# DAC7828_main_V10101010.net
KiCad netlist of a schematic drawn in Altium Designer
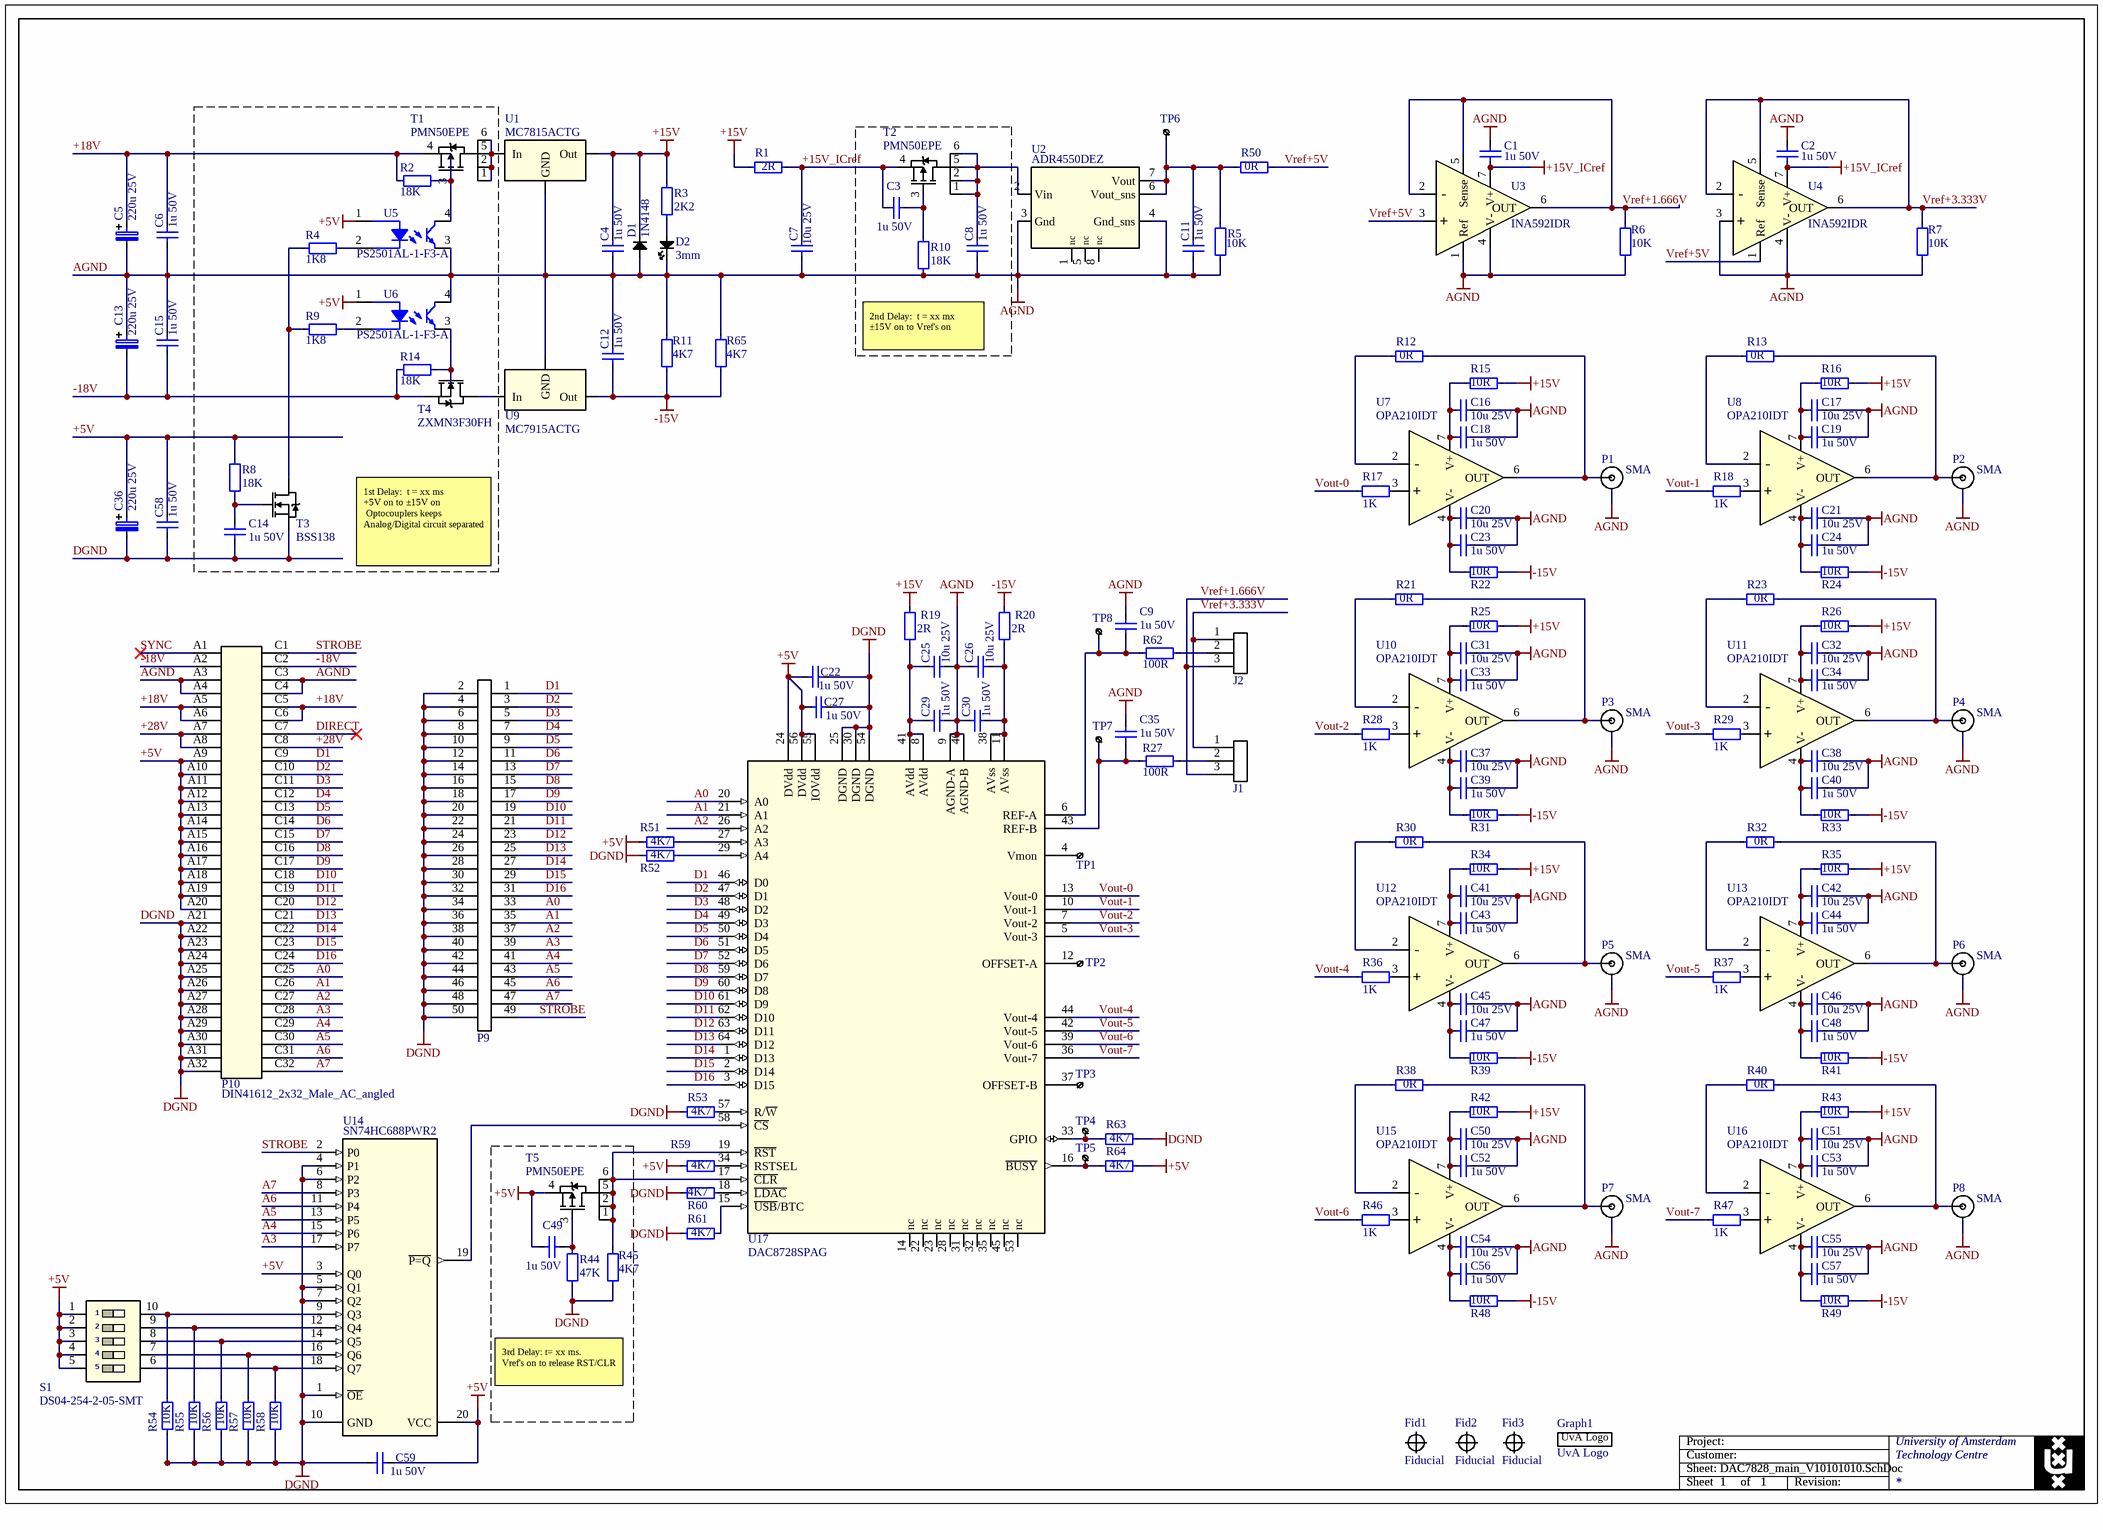
[diagram p0: DAC7828_main_V10101010.SchDoc]

(export (version "E")
  (design (tool "Eeschema 10.0.6"))
  (components
    (comp (ref "C1")
      (value "1u 50V")
      (footprint "cap0603MD")
      (fields
        (field (name "VOLTAGE") "50V")
        (field (name "AUTHOR") "Twe")
        (field (name "CHECKED BY") "Unchecked")
      )
      (libsource (lib "TC_Parts") (part "capacitor"))
    )
    (comp (ref "C2")
      (value "1u 50V")
      (footprint "cap0603MD")
      (fields
        (field (name "VOLTAGE") "50V")
        (field (name "AUTHOR") "Twe")
        (field (name "CHECKED BY") "Unchecked")
      )
      (libsource (lib "TC_Parts") (part "capacitor"))
    )
    (comp (ref "C3")
      (value "1u 50V")
      (footprint "cap0603MD")
      (fields
        (field (name "VOLTAGE") "50V")
        (field (name "AUTHOR") "Twe")
        (field (name "CHECKED BY") "Unchecked")
      )
      (libsource (lib "TC_Parts") (part "capacitor"))
    )
    (comp (ref "C4")
      (value "1u 50V")
      (footprint "cap0603MD")
      (fields
        (field (name "VOLTAGE") "50V")
        (field (name "AUTHOR") "Twe")
        (field (name "CHECKED BY") "Unchecked")
      )
      (libsource (lib "TC_Parts") (part "capacitor"))
    )
    (comp (ref "C5")
      (value "220u 25V")
      (footprint "capAluSmd_d8H10mm")
      (description "Cap Alu SMD d8h11, ±20%")
      (fields
        (field (name "MANUFACTURER") "Kemet")
        (field (name "VOLTAGE") "25V")
        (field (name "AUTHOR") "EB")
        (field (name "CHECKED BY") "Unchecked")
      )
      (libsource (lib "TC_Parts") (part "capuni"))
    )
    (comp (ref "C6")
      (value "1u 50V")
      (footprint "cap0603MD")
      (fields
        (field (name "VOLTAGE") "50V")
        (field (name "AUTHOR") "Twe")
        (field (name "CHECKED BY") "Unchecked")
      )
      (libsource (lib "TC_Parts") (part "capacitor"))
    )
    (comp (ref "C7")
      (value "10u 25V")
      (footprint "cap0805MD")
      (fields
        (field (name "VOLTAGE") "25V")
        (field (name "AUTHOR") "EB")
        (field (name "CHECKED BY") "Unchecked")
      )
      (libsource (lib "TC_Parts") (part "capacitor"))
    )
    (comp (ref "C8")
      (value "1u 50V")
      (footprint "cap0603MD")
      (fields
        (field (name "VOLTAGE") "50V")
        (field (name "AUTHOR") "Twe")
        (field (name "CHECKED BY") "Unchecked")
      )
      (libsource (lib "TC_Parts") (part "capacitor"))
    )
    (comp (ref "C9")
      (value "1u 50V")
      (footprint "cap0603MD")
      (fields
        (field (name "VOLTAGE") "50V")
        (field (name "AUTHOR") "Twe")
        (field (name "CHECKED BY") "Unchecked")
      )
      (libsource (lib "TC_Parts") (part "capacitor"))
    )
    (comp (ref "C11")
      (value "1u 50V")
      (footprint "cap0603MD")
      (fields
        (field (name "VOLTAGE") "50V")
        (field (name "AUTHOR") "Twe")
        (field (name "CHECKED BY") "Unchecked")
      )
      (libsource (lib "TC_Parts") (part "capacitor"))
    )
    (comp (ref "C12")
      (value "1u 50V")
      (footprint "cap0603MD")
      (fields
        (field (name "VOLTAGE") "50V")
        (field (name "AUTHOR") "Twe")
        (field (name "CHECKED BY") "Unchecked")
      )
      (libsource (lib "TC_Parts") (part "capacitor"))
    )
    (comp (ref "C13")
      (value "220u 25V")
      (footprint "capAluSmd_d8H10mm")
      (description "Cap Alu SMD d8h11, ±20%")
      (fields
        (field (name "MANUFACTURER") "Kemet")
        (field (name "VOLTAGE") "25V")
        (field (name "AUTHOR") "EB")
        (field (name "CHECKED BY") "Unchecked")
      )
      (libsource (lib "TC_Parts") (part "capuni"))
    )
    (comp (ref "C14")
      (value "1u 50V")
      (footprint "cap0603MD")
      (fields
        (field (name "VOLTAGE") "50V")
        (field (name "AUTHOR") "Twe")
        (field (name "CHECKED BY") "Unchecked")
      )
      (libsource (lib "TC_Parts") (part "capacitor"))
    )
    (comp (ref "C15")
      (value "1u 50V")
      (footprint "cap0603MD")
      (fields
        (field (name "VOLTAGE") "50V")
        (field (name "AUTHOR") "Twe")
        (field (name "CHECKED BY") "Unchecked")
      )
      (libsource (lib "TC_Parts") (part "capacitor"))
    )
    (comp (ref "C16")
      (value "10u 25V")
      (footprint "cap0805MD")
      (fields
        (field (name "VOLTAGE") "25V")
        (field (name "AUTHOR") "EB")
        (field (name "CHECKED BY") "Unchecked")
      )
      (libsource (lib "TC_Parts") (part "capacitor"))
    )
    (comp (ref "C17")
      (value "10u 25V")
      (footprint "cap0805MD")
      (fields
        (field (name "VOLTAGE") "25V")
        (field (name "AUTHOR") "EB")
        (field (name "CHECKED BY") "Unchecked")
      )
      (libsource (lib "TC_Parts") (part "capacitor"))
    )
    (comp (ref "C18")
      (value "1u 50V")
      (footprint "cap0603MD")
      (fields
        (field (name "VOLTAGE") "50V")
        (field (name "AUTHOR") "Twe")
        (field (name "CHECKED BY") "Unchecked")
      )
      (libsource (lib "TC_Parts") (part "capacitor"))
    )
    (comp (ref "C19")
      (value "1u 50V")
      (footprint "cap0603MD")
      (fields
        (field (name "VOLTAGE") "50V")
        (field (name "AUTHOR") "Twe")
        (field (name "CHECKED BY") "Unchecked")
      )
      (libsource (lib "TC_Parts") (part "capacitor"))
    )
    (comp (ref "C20")
      (value "10u 25V")
      (footprint "cap0805MD")
      (fields
        (field (name "VOLTAGE") "25V")
        (field (name "AUTHOR") "EB")
        (field (name "CHECKED BY") "Unchecked")
      )
      (libsource (lib "TC_Parts") (part "capacitor"))
    )
    (comp (ref "C21")
      (value "10u 25V")
      (footprint "cap0805MD")
      (fields
        (field (name "VOLTAGE") "25V")
        (field (name "AUTHOR") "EB")
        (field (name "CHECKED BY") "Unchecked")
      )
      (libsource (lib "TC_Parts") (part "capacitor"))
    )
    (comp (ref "C22")
      (value "1u 50V")
      (footprint "cap0603MD")
      (fields
        (field (name "VOLTAGE") "50V")
        (field (name "AUTHOR") "Twe")
        (field (name "CHECKED BY") "Unchecked")
      )
      (libsource (lib "TC_Parts") (part "capacitor"))
    )
    (comp (ref "C23")
      (value "1u 50V")
      (footprint "cap0603MD")
      (fields
        (field (name "VOLTAGE") "50V")
        (field (name "AUTHOR") "Twe")
        (field (name "CHECKED BY") "Unchecked")
      )
      (libsource (lib "TC_Parts") (part "capacitor"))
    )
    (comp (ref "C24")
      (value "1u 50V")
      (footprint "cap0603MD")
      (fields
        (field (name "VOLTAGE") "50V")
        (field (name "AUTHOR") "Twe")
        (field (name "CHECKED BY") "Unchecked")
      )
      (libsource (lib "TC_Parts") (part "capacitor"))
    )
    (comp (ref "C25")
      (value "10u 25V")
      (footprint "cap0805MD")
      (fields
        (field (name "VOLTAGE") "25V")
        (field (name "AUTHOR") "EB")
        (field (name "CHECKED BY") "Unchecked")
      )
      (libsource (lib "TC_Parts") (part "capacitor"))
    )
    (comp (ref "C26")
      (value "10u 25V")
      (footprint "cap0805MD")
      (fields
        (field (name "VOLTAGE") "25V")
        (field (name "AUTHOR") "EB")
        (field (name "CHECKED BY") "Unchecked")
      )
      (libsource (lib "TC_Parts") (part "capacitor"))
    )
    (comp (ref "C27")
      (value "1u 50V")
      (footprint "cap0603MD")
      (fields
        (field (name "VOLTAGE") "50V")
        (field (name "AUTHOR") "Twe")
        (field (name "CHECKED BY") "Unchecked")
      )
      (libsource (lib "TC_Parts") (part "capacitor"))
    )
    (comp (ref "C29")
      (value "1u 50V")
      (footprint "cap0603MD")
      (fields
        (field (name "VOLTAGE") "50V")
        (field (name "AUTHOR") "Twe")
        (field (name "CHECKED BY") "Unchecked")
      )
      (libsource (lib "TC_Parts") (part "capacitor"))
    )
    (comp (ref "C30")
      (value "1u 50V")
      (footprint "cap0603MD")
      (fields
        (field (name "VOLTAGE") "50V")
        (field (name "AUTHOR") "Twe")
        (field (name "CHECKED BY") "Unchecked")
      )
      (libsource (lib "TC_Parts") (part "capacitor"))
    )
    (comp (ref "C31")
      (value "10u 25V")
      (footprint "cap0805MD")
      (fields
        (field (name "VOLTAGE") "25V")
        (field (name "AUTHOR") "EB")
        (field (name "CHECKED BY") "Unchecked")
      )
      (libsource (lib "TC_Parts") (part "capacitor"))
    )
    (comp (ref "C32")
      (value "10u 25V")
      (footprint "cap0805MD")
      (fields
        (field (name "VOLTAGE") "25V")
        (field (name "AUTHOR") "EB")
        (field (name "CHECKED BY") "Unchecked")
      )
      (libsource (lib "TC_Parts") (part "capacitor"))
    )
    (comp (ref "C33")
      (value "1u 50V")
      (footprint "cap0603MD")
      (fields
        (field (name "VOLTAGE") "50V")
        (field (name "AUTHOR") "Twe")
        (field (name "CHECKED BY") "Unchecked")
      )
      (libsource (lib "TC_Parts") (part "capacitor"))
    )
    (comp (ref "C34")
      (value "1u 50V")
      (footprint "cap0603MD")
      (fields
        (field (name "VOLTAGE") "50V")
        (field (name "AUTHOR") "Twe")
        (field (name "CHECKED BY") "Unchecked")
      )
      (libsource (lib "TC_Parts") (part "capacitor"))
    )
    (comp (ref "C35")
      (value "1u 50V")
      (footprint "cap0603MD")
      (fields
        (field (name "VOLTAGE") "50V")
        (field (name "AUTHOR") "Twe")
        (field (name "CHECKED BY") "Unchecked")
      )
      (libsource (lib "TC_Parts") (part "capacitor"))
    )
    (comp (ref "C36")
      (value "220u 25V")
      (footprint "capAluSmd_d8H10mm")
      (description "Cap Alu SMD d8h11, ±20%")
      (fields
        (field (name "MANUFACTURER") "Kemet")
        (field (name "VOLTAGE") "25V")
        (field (name "AUTHOR") "EB")
        (field (name "CHECKED BY") "Unchecked")
      )
      (libsource (lib "TC_Parts") (part "capuni"))
    )
    (comp (ref "C37")
      (value "10u 25V")
      (footprint "cap0805MD")
      (fields
        (field (name "VOLTAGE") "25V")
        (field (name "AUTHOR") "EB")
        (field (name "CHECKED BY") "Unchecked")
      )
      (libsource (lib "TC_Parts") (part "capacitor"))
    )
    (comp (ref "C38")
      (value "10u 25V")
      (footprint "cap0805MD")
      (fields
        (field (name "VOLTAGE") "25V")
        (field (name "AUTHOR") "EB")
        (field (name "CHECKED BY") "Unchecked")
      )
      (libsource (lib "TC_Parts") (part "capacitor"))
    )
    (comp (ref "C39")
      (value "1u 50V")
      (footprint "cap0603MD")
      (fields
        (field (name "VOLTAGE") "50V")
        (field (name "AUTHOR") "Twe")
        (field (name "CHECKED BY") "Unchecked")
      )
      (libsource (lib "TC_Parts") (part "capacitor"))
    )
    (comp (ref "C40")
      (value "1u 50V")
      (footprint "cap0603MD")
      (fields
        (field (name "VOLTAGE") "50V")
        (field (name "AUTHOR") "Twe")
        (field (name "CHECKED BY") "Unchecked")
      )
      (libsource (lib "TC_Parts") (part "capacitor"))
    )
    (comp (ref "C41")
      (value "10u 25V")
      (footprint "cap0805MD")
      (fields
        (field (name "VOLTAGE") "25V")
        (field (name "AUTHOR") "EB")
        (field (name "CHECKED BY") "Unchecked")
      )
      (libsource (lib "TC_Parts") (part "capacitor"))
    )
    (comp (ref "C42")
      (value "10u 25V")
      (footprint "cap0805MD")
      (fields
        (field (name "VOLTAGE") "25V")
        (field (name "AUTHOR") "EB")
        (field (name "CHECKED BY") "Unchecked")
      )
      (libsource (lib "TC_Parts") (part "capacitor"))
    )
    (comp (ref "C43")
      (value "1u 50V")
      (footprint "cap0603MD")
      (fields
        (field (name "VOLTAGE") "50V")
        (field (name "AUTHOR") "Twe")
        (field (name "CHECKED BY") "Unchecked")
      )
      (libsource (lib "TC_Parts") (part "capacitor"))
    )
    (comp (ref "C44")
      (value "1u 50V")
      (footprint "cap0603MD")
      (fields
        (field (name "VOLTAGE") "50V")
        (field (name "AUTHOR") "Twe")
        (field (name "CHECKED BY") "Unchecked")
      )
      (libsource (lib "TC_Parts") (part "capacitor"))
    )
    (comp (ref "C45")
      (value "10u 25V")
      (footprint "cap0805MD")
      (fields
        (field (name "VOLTAGE") "25V")
        (field (name "AUTHOR") "EB")
        (field (name "CHECKED BY") "Unchecked")
      )
      (libsource (lib "TC_Parts") (part "capacitor"))
    )
    (comp (ref "C46")
      (value "10u 25V")
      (footprint "cap0805MD")
      (fields
        (field (name "VOLTAGE") "25V")
        (field (name "AUTHOR") "EB")
        (field (name "CHECKED BY") "Unchecked")
      )
      (libsource (lib "TC_Parts") (part "capacitor"))
    )
    (comp (ref "C47")
      (value "1u 50V")
      (footprint "cap0603MD")
      (fields
        (field (name "VOLTAGE") "50V")
        (field (name "AUTHOR") "Twe")
        (field (name "CHECKED BY") "Unchecked")
      )
      (libsource (lib "TC_Parts") (part "capacitor"))
    )
    (comp (ref "C48")
      (value "1u 50V")
      (footprint "cap0603MD")
      (fields
        (field (name "VOLTAGE") "50V")
        (field (name "AUTHOR") "Twe")
        (field (name "CHECKED BY") "Unchecked")
      )
      (libsource (lib "TC_Parts") (part "capacitor"))
    )
    (comp (ref "C49")
      (value "1u 50V")
      (footprint "cap0603MD")
      (fields
        (field (name "VOLTAGE") "50V")
        (field (name "AUTHOR") "Twe")
        (field (name "CHECKED BY") "Unchecked")
      )
      (libsource (lib "TC_Parts") (part "capacitor"))
    )
    (comp (ref "C50")
      (value "10u 25V")
      (footprint "cap0805MD")
      (fields
        (field (name "VOLTAGE") "25V")
        (field (name "AUTHOR") "EB")
        (field (name "CHECKED BY") "Unchecked")
      )
      (libsource (lib "TC_Parts") (part "capacitor"))
    )
    (comp (ref "C51")
      (value "10u 25V")
      (footprint "cap0805MD")
      (fields
        (field (name "VOLTAGE") "25V")
        (field (name "AUTHOR") "EB")
        (field (name "CHECKED BY") "Unchecked")
      )
      (libsource (lib "TC_Parts") (part "capacitor"))
    )
    (comp (ref "C52")
      (value "1u 50V")
      (footprint "cap0603MD")
      (fields
        (field (name "VOLTAGE") "50V")
        (field (name "AUTHOR") "Twe")
        (field (name "CHECKED BY") "Unchecked")
      )
      (libsource (lib "TC_Parts") (part "capacitor"))
    )
    (comp (ref "C53")
      (value "1u 50V")
      (footprint "cap0603MD")
      (fields
        (field (name "VOLTAGE") "50V")
        (field (name "AUTHOR") "Twe")
        (field (name "CHECKED BY") "Unchecked")
      )
      (libsource (lib "TC_Parts") (part "capacitor"))
    )
    (comp (ref "C54")
      (value "10u 25V")
      (footprint "cap0805MD")
      (fields
        (field (name "VOLTAGE") "25V")
        (field (name "AUTHOR") "EB")
        (field (name "CHECKED BY") "Unchecked")
      )
      (libsource (lib "TC_Parts") (part "capacitor"))
    )
    (comp (ref "C55")
      (value "10u 25V")
      (footprint "cap0805MD")
      (fields
        (field (name "VOLTAGE") "25V")
        (field (name "AUTHOR") "EB")
        (field (name "CHECKED BY") "Unchecked")
      )
      (libsource (lib "TC_Parts") (part "capacitor"))
    )
    (comp (ref "C56")
      (value "1u 50V")
      (footprint "cap0603MD")
      (fields
        (field (name "VOLTAGE") "50V")
        (field (name "AUTHOR") "Twe")
        (field (name "CHECKED BY") "Unchecked")
      )
      (libsource (lib "TC_Parts") (part "capacitor"))
    )
    (comp (ref "C57")
      (value "1u 50V")
      (footprint "cap0603MD")
      (fields
        (field (name "VOLTAGE") "50V")
        (field (name "AUTHOR") "Twe")
        (field (name "CHECKED BY") "Unchecked")
      )
      (libsource (lib "TC_Parts") (part "capacitor"))
    )
    (comp (ref "C58")
      (value "1u 50V")
      (footprint "cap0603MD")
      (fields
        (field (name "VOLTAGE") "50V")
        (field (name "AUTHOR") "Twe")
        (field (name "CHECKED BY") "Unchecked")
      )
      (libsource (lib "TC_Parts") (part "capacitor"))
    )
    (comp (ref "C59")
      (value "1u 50V")
      (footprint "cap0603MD")
      (fields
        (field (name "VOLTAGE") "50V")
        (field (name "AUTHOR") "Twe")
        (field (name "CHECKED BY") "Unchecked")
      )
      (libsource (lib "TC_Parts") (part "capacitor"))
    )
    (comp (ref "D1")
      (value "1N4148")
      (footprint "SOD2513X100N")
      (description "Small Signal Diode, Single, 100 V, 150 mA, 1 V, 4 ns, 350 mA")
      (fields
        (field (name "MANUFACTURER") "Multicomp")
        (field (name "AUTHOR") "Twe")
        (field (name "CHECKED BY") "PCB")
      )
      (libsource (lib "TC_Parts") (part "diode_CA"))
    )
    (comp (ref "D2")
      (value "3mm")
      (footprint "LED_3MM_PCB_EDGE_SMD")
      (description "Generic 3mm LED Footprint PCB Edge SMD Pads")
      (fields (field (name "AUTHOR") "EB") (field (name "CHECKED BY") "Unchecked"))
      (libsource (lib "TC_Parts") (part "LED_CA"))
    )
    (comp (ref "Fid1")
      (value "Fiducial")
      (footprint "fiducial")
      (fields (field (name "AUTHOR") "Twe") (field (name "CHECKED BY") "PCB"))
      (libsource (lib "TC_Parts") (part "fiducial"))
    )
    (comp (ref "Fid2")
      (value "Fiducial")
      (footprint "fiducial")
      (fields (field (name "AUTHOR") "Twe") (field (name "CHECKED BY") "PCB"))
      (libsource (lib "TC_Parts") (part "fiducial"))
    )
    (comp (ref "Fid3")
      (value "Fiducial")
      (footprint "fiducial")
      (fields (field (name "AUTHOR") "Twe") (field (name "CHECKED BY") "PCB"))
      (libsource (lib "TC_Parts") (part "fiducial"))
    )
    (comp (ref "Graph1")
      (value "UvA Logo")
      (footprint "UvA_Logo")
      (description "University of Amsterdam Logo")
      (fields (field (name "AUTHOR") "Twe") (field (name "CHECKED BY") "PCB"))
      (libsource (lib "TC_Parts") (part "UvA_Logo"))
    )
    (comp (ref "J1")
      (value "Header 2.54")
      (footprint "Header254-1x3")
      (description "Header 2.54p 1x3")
      (fields (field (name "AUTHOR") "Twe") (field (name "CHECKED BY") "PCB"))
      (libsource (lib "TC_Parts") (part "header1x3"))
    )
    (comp (ref "J2")
      (value "Header 2.54")
      (footprint "Header254-1x3")
      (description "Header 2.54p 1x3")
      (fields (field (name "AUTHOR") "Twe") (field (name "CHECKED BY") "PCB"))
      (libsource (lib "TC_Parts") (part "header1x3"))
    )
    (comp (ref "P1")
      (value "SMA")
      (footprint "619540-1")
      (description "SMA right angle through hole, 19mm, 50 Ohm")
      (fields
        (field (name "MANUFACTURER") "TE connectivity")
        (field (name "AUTHOR") "EB")
        (field (name "CHECKED BY") "Unchecked")
      )
      (libsource (lib "TC_Parts") (part "SMA"))
    )
    (comp (ref "P2")
      (value "SMA")
      (footprint "619540-1")
      (description "SMA right angle through hole, 19mm, 50 Ohm")
      (fields
        (field (name "MANUFACTURER") "TE connectivity")
        (field (name "AUTHOR") "EB")
        (field (name "CHECKED BY") "Unchecked")
      )
      (libsource (lib "TC_Parts") (part "SMA"))
    )
    (comp (ref "P3")
      (value "SMA")
      (footprint "619540-1")
      (description "SMA right angle through hole, 19mm, 50 Ohm")
      (fields
        (field (name "MANUFACTURER") "TE connectivity")
        (field (name "AUTHOR") "EB")
        (field (name "CHECKED BY") "Unchecked")
      )
      (libsource (lib "TC_Parts") (part "SMA"))
    )
    (comp (ref "P4")
      (value "SMA")
      (footprint "619540-1")
      (description "SMA right angle through hole, 19mm, 50 Ohm")
      (fields
        (field (name "MANUFACTURER") "TE connectivity")
        (field (name "AUTHOR") "EB")
        (field (name "CHECKED BY") "Unchecked")
      )
      (libsource (lib "TC_Parts") (part "SMA"))
    )
    (comp (ref "P5")
      (value "SMA")
      (footprint "619540-1")
      (description "SMA right angle through hole, 19mm, 50 Ohm")
      (fields
        (field (name "MANUFACTURER") "TE connectivity")
        (field (name "AUTHOR") "EB")
        (field (name "CHECKED BY") "Unchecked")
      )
      (libsource (lib "TC_Parts") (part "SMA"))
    )
    (comp (ref "P6")
      (value "SMA")
      (footprint "619540-1")
      (description "SMA right angle through hole, 19mm, 50 Ohm")
      (fields
        (field (name "MANUFACTURER") "TE connectivity")
        (field (name "AUTHOR") "EB")
        (field (name "CHECKED BY") "Unchecked")
      )
      (libsource (lib "TC_Parts") (part "SMA"))
    )
    (comp (ref "P7")
      (value "SMA")
      (footprint "619540-1")
      (description "SMA right angle through hole, 19mm, 50 Ohm")
      (fields
        (field (name "MANUFACTURER") "TE connectivity")
        (field (name "AUTHOR") "EB")
        (field (name "CHECKED BY") "Unchecked")
      )
      (libsource (lib "TC_Parts") (part "SMA"))
    )
    (comp (ref "P8")
      (value "SMA")
      (footprint "619540-1")
      (description "SMA right angle through hole, 19mm, 50 Ohm")
      (fields
        (field (name "MANUFACTURER") "TE connectivity")
        (field (name "AUTHOR") "EB")
        (field (name "CHECKED BY") "Unchecked")
      )
      (libsource (lib "TC_Parts") (part "SMA"))
    )
    (comp (ref "P9")
      (value "Header 2.54")
      (footprint "Header254-2x25")
      (description "Header 2.54p 2x25")
      (fields
        (field (name "MANUFACTURER") "Multicomp")
        (field (name "AUTHOR") "EB")
        (field (name "CHECKED BY") "Unchecked")
      )
      (libsource (lib "TC_Parts") (part "header2x25"))
    )
    (comp (ref "P10")
      (value "DIN41612_2x32_Male_AC_angled")
      (footprint "DIN41612_2x32_Male_AC_angled")
      (fields
        (field (name "MANUFACTURER") "Hartman")
        (field (name "AUTHOR") "EB")
        (field (name "CHECKED BY") "Unchecked")
      )
      (libsource (lib "TC_Parts") (part "DIN41612_2x32_Male_AC_Full"))
    )
    (comp (ref "R1")
      (value "2R")
      (footprint "res0603MD")
      (fields (field (name "AUTHOR") "EB") (field (name "CHECKED BY") "Unchecked"))
      (libsource (lib "") (part "resistor_3"))
    )
    (comp (ref "R2")
      (value "18K")
      (footprint "res0603MD")
      (fields (field (name "AUTHOR") "Twe") (field (name "CHECKED BY") "Unchecked"))
      (libsource (lib "") (part "resistor_1"))
    )
    (comp (ref "R3")
      (value "2K2")
      (footprint "res0603MD")
      (fields (field (name "AUTHOR") "Twe") (field (name "CHECKED BY") "Unchecked"))
      (libsource (lib "") (part "resistor_2"))
    )
    (comp (ref "R4")
      (value "1K8")
      (footprint "res0603MD")
      (fields (field (name "AUTHOR") "Twe") (field (name "CHECKED BY") "Unchecked"))
      (libsource (lib "") (part "resistor_1"))
    )
    (comp (ref "R5")
      (value "10K")
      (footprint "res0603MD")
      (fields (field (name "AUTHOR") "TvR") (field (name "CHECKED BY") "Unchecked"))
      (libsource (lib "") (part "resistor_2"))
    )
    (comp (ref "R6")
      (value "10K")
      (footprint "res0603MD")
      (fields (field (name "AUTHOR") "TvR") (field (name "CHECKED BY") "Unchecked"))
      (libsource (lib "") (part "resistor_2"))
    )
    (comp (ref "R7")
      (value "10K")
      (footprint "res0603MD")
      (fields (field (name "AUTHOR") "TvR") (field (name "CHECKED BY") "Unchecked"))
      (libsource (lib "") (part "resistor_2"))
    )
    (comp (ref "R8")
      (value "18K")
      (footprint "res0603MD")
      (fields (field (name "AUTHOR") "Twe") (field (name "CHECKED BY") "Unchecked"))
      (libsource (lib "") (part "resistor_2"))
    )
    (comp (ref "R9")
      (value "1K8")
      (footprint "res0603MD")
      (fields (field (name "AUTHOR") "Twe") (field (name "CHECKED BY") "Unchecked"))
      (libsource (lib "") (part "resistor_1"))
    )
    (comp (ref "R10")
      (value "18K")
      (footprint "res0603MD")
      (fields (field (name "AUTHOR") "Twe") (field (name "CHECKED BY") "Unchecked"))
      (libsource (lib "") (part "resistor_2"))
    )
    (comp (ref "R11")
      (value "4K7")
      (footprint "res0603MD")
      (fields (field (name "AUTHOR") "Twe") (field (name "CHECKED BY") "Unchecked"))
      (libsource (lib "") (part "resistor_2"))
    )
    (comp (ref "R12")
      (value "0R")
      (footprint "res0603MD")
      (fields (field (name "AUTHOR") "Twe") (field (name "CHECKED BY") "Unchecked"))
      (libsource (lib "") (part "resistor_1"))
    )
    (comp (ref "R13")
      (value "0R")
      (footprint "res0603MD")
      (fields (field (name "AUTHOR") "Twe") (field (name "CHECKED BY") "Unchecked"))
      (libsource (lib "") (part "resistor_1"))
    )
    (comp (ref "R14")
      (value "18K")
      (footprint "res0603MD")
      (fields (field (name "AUTHOR") "Twe") (field (name "CHECKED BY") "Unchecked"))
      (libsource (lib "") (part "resistor_1"))
    )
    (comp (ref "R15")
      (value "10R")
      (footprint "res0603MD")
      (fields (field (name "AUTHOR") "Twe") (field (name "CHECKED BY") "Unchecked"))
      (libsource (lib "TC_Parts") (part "resistor"))
    )
    (comp (ref "R16")
      (value "10R")
      (footprint "res0603MD")
      (fields (field (name "AUTHOR") "Twe") (field (name "CHECKED BY") "Unchecked"))
      (libsource (lib "TC_Parts") (part "resistor"))
    )
    (comp (ref "R17")
      (value "1K")
      (footprint "res0603MD")
      (fields (field (name "AUTHOR") "Twe") (field (name "CHECKED BY") "Unchecked"))
      (libsource (lib "") (part "resistor_1"))
    )
    (comp (ref "R18")
      (value "1K")
      (footprint "res0603MD")
      (fields (field (name "AUTHOR") "Twe") (field (name "CHECKED BY") "Unchecked"))
      (libsource (lib "") (part "resistor_1"))
    )
    (comp (ref "R19")
      (value "2R")
      (footprint "res0603MD")
      (fields (field (name "AUTHOR") "EB") (field (name "CHECKED BY") "Unchecked"))
      (libsource (lib "") (part "resistor_2"))
    )
    (comp (ref "R20")
      (value "2R")
      (footprint "res0603MD")
      (fields (field (name "AUTHOR") "EB") (field (name "CHECKED BY") "Unchecked"))
      (libsource (lib "") (part "resistor_2"))
    )
    (comp (ref "R21")
      (value "0R")
      (footprint "res0603MD")
      (fields (field (name "AUTHOR") "Twe") (field (name "CHECKED BY") "Unchecked"))
      (libsource (lib "") (part "resistor_1"))
    )
    (comp (ref "R22")
      (value "10R")
      (footprint "res0603MD")
      (fields (field (name "AUTHOR") "Twe") (field (name "CHECKED BY") "Unchecked"))
      (libsource (lib "TC_Parts") (part "resistor"))
    )
    (comp (ref "R23")
      (value "0R")
      (footprint "res0603MD")
      (fields (field (name "AUTHOR") "Twe") (field (name "CHECKED BY") "Unchecked"))
      (libsource (lib "") (part "resistor_1"))
    )
    (comp (ref "R24")
      (value "10R")
      (footprint "res0603MD")
      (fields (field (name "AUTHOR") "Twe") (field (name "CHECKED BY") "Unchecked"))
      (libsource (lib "TC_Parts") (part "resistor"))
    )
    (comp (ref "R25")
      (value "10R")
      (footprint "res0603MD")
      (fields (field (name "AUTHOR") "Twe") (field (name "CHECKED BY") "Unchecked"))
      (libsource (lib "TC_Parts") (part "resistor"))
    )
    (comp (ref "R26")
      (value "10R")
      (footprint "res0603MD")
      (fields (field (name "AUTHOR") "Twe") (field (name "CHECKED BY") "Unchecked"))
      (libsource (lib "TC_Parts") (part "resistor"))
    )
    (comp (ref "R27")
      (value "100R")
      (footprint "res0603MD")
      (fields (field (name "AUTHOR") "TvR") (field (name "CHECKED BY") "Unchecked"))
      (libsource (lib "") (part "resistor_1"))
    )
    (comp (ref "R28")
      (value "1K")
      (footprint "res0603MD")
      (fields (field (name "AUTHOR") "Twe") (field (name "CHECKED BY") "Unchecked"))
      (libsource (lib "") (part "resistor_1"))
    )
    (comp (ref "R29")
      (value "1K")
      (footprint "res0603MD")
      (fields (field (name "AUTHOR") "Twe") (field (name "CHECKED BY") "Unchecked"))
      (libsource (lib "") (part "resistor_1"))
    )
    (comp (ref "R30")
      (value "0R")
      (footprint "res0603MD")
      (fields (field (name "AUTHOR") "Twe") (field (name "CHECKED BY") "Unchecked"))
      (libsource (lib "") (part "resistor_1"))
    )
    (comp (ref "R31")
      (value "10R")
      (footprint "res0603MD")
      (fields (field (name "AUTHOR") "Twe") (field (name "CHECKED BY") "Unchecked"))
      (libsource (lib "TC_Parts") (part "resistor"))
    )
    (comp (ref "R32")
      (value "0R")
      (footprint "res0603MD")
      (fields (field (name "AUTHOR") "Twe") (field (name "CHECKED BY") "Unchecked"))
      (libsource (lib "") (part "resistor_1"))
    )
    (comp (ref "R33")
      (value "10R")
      (footprint "res0603MD")
      (fields (field (name "AUTHOR") "Twe") (field (name "CHECKED BY") "Unchecked"))
      (libsource (lib "TC_Parts") (part "resistor"))
    )
    (comp (ref "R34")
      (value "10R")
      (footprint "res0603MD")
      (fields (field (name "AUTHOR") "Twe") (field (name "CHECKED BY") "Unchecked"))
      (libsource (lib "TC_Parts") (part "resistor"))
    )
    (comp (ref "R35")
      (value "10R")
      (footprint "res0603MD")
      (fields (field (name "AUTHOR") "Twe") (field (name "CHECKED BY") "Unchecked"))
      (libsource (lib "TC_Parts") (part "resistor"))
    )
    (comp (ref "R36")
      (value "1K")
      (footprint "res0603MD")
      (fields (field (name "AUTHOR") "Twe") (field (name "CHECKED BY") "Unchecked"))
      (libsource (lib "") (part "resistor_1"))
    )
    (comp (ref "R37")
      (value "1K")
      (footprint "res0603MD")
      (fields (field (name "AUTHOR") "Twe") (field (name "CHECKED BY") "Unchecked"))
      (libsource (lib "") (part "resistor_1"))
    )
    (comp (ref "R38")
      (value "0R")
      (footprint "res0603MD")
      (fields (field (name "AUTHOR") "Twe") (field (name "CHECKED BY") "Unchecked"))
      (libsource (lib "") (part "resistor_1"))
    )
    (comp (ref "R39")
      (value "10R")
      (footprint "res0603MD")
      (fields (field (name "AUTHOR") "Twe") (field (name "CHECKED BY") "Unchecked"))
      (libsource (lib "TC_Parts") (part "resistor"))
    )
    (comp (ref "R40")
      (value "0R")
      (footprint "res0603MD")
      (fields (field (name "AUTHOR") "Twe") (field (name "CHECKED BY") "Unchecked"))
      (libsource (lib "") (part "resistor_1"))
    )
    (comp (ref "R41")
      (value "10R")
      (footprint "res0603MD")
      (fields (field (name "AUTHOR") "Twe") (field (name "CHECKED BY") "Unchecked"))
      (libsource (lib "TC_Parts") (part "resistor"))
    )
    (comp (ref "R42")
      (value "10R")
      (footprint "res0603MD")
      (fields (field (name "AUTHOR") "Twe") (field (name "CHECKED BY") "Unchecked"))
      (libsource (lib "TC_Parts") (part "resistor"))
    )
    (comp (ref "R43")
      (value "10R")
      (footprint "res0603MD")
      (fields (field (name "AUTHOR") "Twe") (field (name "CHECKED BY") "Unchecked"))
      (libsource (lib "TC_Parts") (part "resistor"))
    )
    (comp (ref "R44")
      (value "47K")
      (footprint "res0603MD")
      (fields (field (name "AUTHOR") "Twe") (field (name "CHECKED BY") "Unchecked"))
      (libsource (lib "") (part "resistor_2"))
    )
    (comp (ref "R45")
      (value "4K7")
      (footprint "res0603MD")
      (fields (field (name "AUTHOR") "Twe") (field (name "CHECKED BY") "Unchecked"))
      (libsource (lib "") (part "resistor_2"))
    )
    (comp (ref "R46")
      (value "1K")
      (footprint "res0603MD")
      (fields (field (name "AUTHOR") "Twe") (field (name "CHECKED BY") "Unchecked"))
      (libsource (lib "") (part "resistor_1"))
    )
    (comp (ref "R47")
      (value "1K")
      (footprint "res0603MD")
      (fields (field (name "AUTHOR") "Twe") (field (name "CHECKED BY") "Unchecked"))
      (libsource (lib "") (part "resistor_1"))
    )
    (comp (ref "R48")
      (value "10R")
      (footprint "res0603MD")
      (fields (field (name "AUTHOR") "Twe") (field (name "CHECKED BY") "Unchecked"))
      (libsource (lib "TC_Parts") (part "resistor"))
    )
    (comp (ref "R49")
      (value "10R")
      (footprint "res0603MD")
      (fields (field (name "AUTHOR") "Twe") (field (name "CHECKED BY") "Unchecked"))
      (libsource (lib "TC_Parts") (part "resistor"))
    )
    (comp (ref "R50")
      (value "0R")
      (footprint "res0603MD")
      (fields (field (name "AUTHOR") "Twe") (field (name "CHECKED BY") "Unchecked"))
      (libsource (lib "") (part "resistor_1"))
    )
    (comp (ref "R51")
      (value "4K7")
      (footprint "res0603MD")
      (fields (field (name "AUTHOR") "Twe") (field (name "CHECKED BY") "Unchecked"))
      (libsource (lib "") (part "resistor_1"))
    )
    (comp (ref "R52")
      (value "4K7")
      (footprint "res0603MD")
      (fields (field (name "AUTHOR") "Twe") (field (name "CHECKED BY") "Unchecked"))
      (libsource (lib "") (part "resistor_1"))
    )
    (comp (ref "R53")
      (value "4K7")
      (footprint "res0603MD")
      (fields (field (name "AUTHOR") "Twe") (field (name "CHECKED BY") "Unchecked"))
      (libsource (lib "") (part "resistor_1"))
    )
    (comp (ref "R54")
      (value "10K")
      (footprint "res0603HD")
      (fields (field (name "AUTHOR") "RoKo") (field (name "CHECKED BY") "Unchecked"))
      (libsource (lib "") (part "resistor_2"))
    )
    (comp (ref "R55")
      (value "10K")
      (footprint "res0603HD")
      (fields (field (name "AUTHOR") "RoKo") (field (name "CHECKED BY") "Unchecked"))
      (libsource (lib "") (part "resistor_2"))
    )
    (comp (ref "R56")
      (value "10K")
      (footprint "res0603HD")
      (fields (field (name "AUTHOR") "RoKo") (field (name "CHECKED BY") "Unchecked"))
      (libsource (lib "") (part "resistor_2"))
    )
    (comp (ref "R57")
      (value "10K")
      (footprint "res0603HD")
      (fields (field (name "AUTHOR") "RoKo") (field (name "CHECKED BY") "Unchecked"))
      (libsource (lib "") (part "resistor_2"))
    )
    (comp (ref "R58")
      (value "10K")
      (footprint "res0603HD")
      (fields (field (name "AUTHOR") "RoKo") (field (name "CHECKED BY") "Unchecked"))
      (libsource (lib "") (part "resistor_2"))
    )
    (comp (ref "R59")
      (value "4K7")
      (footprint "res0603MD")
      (fields (field (name "AUTHOR") "Twe") (field (name "CHECKED BY") "Unchecked"))
      (libsource (lib "") (part "resistor_1"))
    )
    (comp (ref "R60")
      (value "4K7")
      (footprint "res0603MD")
      (fields (field (name "AUTHOR") "Twe") (field (name "CHECKED BY") "Unchecked"))
      (libsource (lib "") (part "resistor_1"))
    )
    (comp (ref "R61")
      (value "4K7")
      (footprint "res0603MD")
      (fields (field (name "AUTHOR") "Twe") (field (name "CHECKED BY") "Unchecked"))
      (libsource (lib "") (part "resistor_1"))
    )
    (comp (ref "R62")
      (value "100R")
      (footprint "res0603MD")
      (fields (field (name "AUTHOR") "TvR") (field (name "CHECKED BY") "Unchecked"))
      (libsource (lib "") (part "resistor_1"))
    )
    (comp (ref "R63")
      (value "4K7")
      (footprint "res0603MD")
      (fields (field (name "AUTHOR") "Twe") (field (name "CHECKED BY") "Unchecked"))
      (libsource (lib "") (part "resistor_1"))
    )
    (comp (ref "R64")
      (value "4K7")
      (footprint "res0603MD")
      (fields (field (name "AUTHOR") "Twe") (field (name "CHECKED BY") "Unchecked"))
      (libsource (lib "") (part "resistor_1"))
    )
    (comp (ref "R65")
      (value "4K7")
      (footprint "res0603MD")
      (fields (field (name "AUTHOR") "Twe") (field (name "CHECKED BY") "Unchecked"))
      (libsource (lib "") (part "resistor_2"))
    )
    (comp (ref "S1")
      (value "DS04-254-2-05-SMT")
      (footprint "DS04-254-2-05-SMT")
      (description "DIP Switch, 5 SPST, SMD")
      (fields
        (field (name "MANUFACTURER") "CUI Devices")
        (field (name "AUTHOR") "EB")
        (field (name "CHECKED BY") "Unchecked")
      )
      (libsource (lib "TC_Parts") (part "DipSwitch_5SPST_DIL"))
    )
    (comp (ref "T1")
      (value "PMN50EPE")
      (footprint "TSOP95P280X110-6N")
      (description "P Channel, MOSFET, -30 V, -6A, 0.045 ohm, SOT457")
      (fields
        (field (name "MANUFACTURER") "NEXPERIA")
        (field (name "AUTHOR") "EB")
        (field (name "CHECKED BY") "Unchecked")
      )
      (libsource (lib "TC_Parts") (part "MOSFET-P-6p-DDGSDD"))
    )
    (comp (ref "T2")
      (value "PMN50EPE")
      (footprint "TSOP95P280X110-6N")
      (description "P Channel, MOSFET, -30 V, -6A, 0.045 ohm, SOT457")
      (fields
        (field (name "MANUFACTURER") "NEXPERIA")
        (field (name "AUTHOR") "EB")
        (field (name "CHECKED BY") "Unchecked")
      )
      (libsource (lib "TC_Parts") (part "MOSFET-P-6p-DDGSDD"))
    )
    (comp (ref "T3")
      (value "BSS138")
      (footprint "SOT95P230X110-3N")
      (description "N-Channel Logic Level Enhancement, 3R5")
      (fields
        (field (name "MANUFACTURER") "ON Semi")
        (field (name "AUTHOR") "TvR")
        (field (name "CHECKED BY") "Unchecked")
      )
      (libsource (lib "TC_Parts") (part "MOSFET-NE-RevD_GSD"))
    )
    (comp (ref "T4")
      (value "ZXMN3F30FH")
      (footprint "SOT95P230X110-3N")
      (description "MOSFET Transistor, N Channel, 4.6 A, 30 V, 65 mohm, 4.5Vgs")
      (fields
        (field (name "MANUFACTURER") "ZETEX")
        (field (name "AUTHOR") "EB")
        (field (name "CHECKED BY") "Unchecked")
      )
      (libsource (lib "TC_Parts") (part "MOSFET-NE-RevD_GSD"))
    )
    (comp (ref "T5")
      (value "PMN50EPE")
      (footprint "TSOP95P280X110-6N")
      (description "P Channel, MOSFET, -30 V, -6A, 0.045 ohm, SOT457")
      (fields
        (field (name "MANUFACTURER") "NEXPERIA")
        (field (name "AUTHOR") "EB")
        (field (name "CHECKED BY") "Unchecked")
      )
      (libsource (lib "TC_Parts") (part "MOSFET-P-6p-DDGSDD"))
    )
    (comp (ref "TP1")
      (value "Testpoint")
      (footprint "Testpoint_1mm")
      (description "Testpoint pad 1mm")
      (fields (field (name "AUTHOR") "Twe") (field (name "CHECKED BY") "PCB"))
      (libsource (lib "TC_Parts") (part "testpoint"))
    )
    (comp (ref "TP2")
      (value "Testpoint")
      (footprint "Testpoint_1mm")
      (description "Testpoint pad 1mm")
      (fields (field (name "AUTHOR") "Twe") (field (name "CHECKED BY") "PCB"))
      (libsource (lib "TC_Parts") (part "testpoint"))
    )
    (comp (ref "TP3")
      (value "Testpoint")
      (footprint "Testpoint_1mm")
      (description "Testpoint pad 1mm")
      (fields (field (name "AUTHOR") "Twe") (field (name "CHECKED BY") "PCB"))
      (libsource (lib "TC_Parts") (part "testpoint"))
    )
    (comp (ref "TP4")
      (value "Testpoint")
      (footprint "Testpoint_1mm")
      (description "Testpoint pad 1mm")
      (fields (field (name "AUTHOR") "Twe") (field (name "CHECKED BY") "PCB"))
      (libsource (lib "TC_Parts") (part "testpoint"))
    )
    (comp (ref "TP5")
      (value "Testpoint")
      (footprint "Testpoint_1mm")
      (description "Testpoint pad 1mm")
      (fields (field (name "AUTHOR") "Twe") (field (name "CHECKED BY") "PCB"))
      (libsource (lib "TC_Parts") (part "testpoint"))
    )
    (comp (ref "TP6")
      (value "Testpoint")
      (footprint "Testpoint_1mm")
      (description "Testpoint pad 1mm")
      (fields (field (name "AUTHOR") "Twe") (field (name "CHECKED BY") "PCB"))
      (libsource (lib "TC_Parts") (part "testpoint"))
    )
    (comp (ref "TP7")
      (value "Testpoint")
      (footprint "Testpoint_1mm")
      (description "Testpoint pad 1mm")
      (fields (field (name "AUTHOR") "Twe") (field (name "CHECKED BY") "PCB"))
      (libsource (lib "TC_Parts") (part "testpoint"))
    )
    (comp (ref "TP8")
      (value "Testpoint")
      (footprint "Testpoint_1mm")
      (description "Testpoint pad 1mm")
      (fields (field (name "AUTHOR") "Twe") (field (name "CHECKED BY") "PCB"))
      (libsource (lib "TC_Parts") (part "testpoint"))
    )
    (comp (ref "U1")
      (value "MC7815ACTG")
      (footprint "TO220-3_FLAT")
      (description "Linear Voltage Regulator,Positive, Fixed, 35V In, 15V And 1A Out")
      (fields
        (field (name "MANUFACTURER") "OnSEMI")
        (field (name "AUTHOR") "EB")
        (field (name "CHECKED BY") "Unchecked")
      )
      (libsource (lib "TC_Parts") (part "LDO_IGO"))
    )
    (comp (ref "U2")
      (value "ADR4550DEZ")
      (footprint "LCCS127P503X450X221-8M")
      (description "Ultralow Noise, High Accuracy\r\nVoltage References")
      (fields
        (field (name "MANUFACTURER") "Analog Devices")
        (field (name "AUTHOR") "EB")
        (field (name "CHECKED BY") "Unchecked")
      )
      (libsource (lib "TC_Parts") (part "ADR4550DEZ"))
    )
    (comp (ref "U3")
      (value "INA592IDR")
      (footprint "SOIC127P600X175-8N")
      (description "INA592 High-Precision, Wide-Bandwidth e-trim™ Difference Amplifier")
      (fields
        (field (name "MANUFACTURER") "Texas Instruments")
        (field (name "AUTHOR") "EB")
        (field (name "CHECKED BY") "Unchecked")
      )
      (libsource (lib "TC_Parts") (part "INA592IDR"))
    )
    (comp (ref "U4")
      (value "INA592IDR")
      (footprint "SOIC127P600X175-8N")
      (description "INA592 High-Precision, Wide-Bandwidth e-trim™ Difference Amplifier")
      (fields
        (field (name "MANUFACTURER") "Texas Instruments")
        (field (name "AUTHOR") "EB")
        (field (name "CHECKED BY") "Unchecked")
      )
      (libsource (lib "TC_Parts") (part "INA592IDR"))
    )
    (comp (ref "U5")
      (value "PS2501AL-1-F3-A")
      (footprint "SOP254P960X380-4N")
      (description "Optocoupler 1ch, Vceo=70V, Ic=30mA, CTR=200-400% @ 5mA")
      (fields
        (field (name "MANUFACTURER") "CEL")
        (field (name "AUTHOR") "EB")
        (field (name "CHECKED BY") "Unchecked")
      )
      (libsource (lib "TC_Parts") (part "OptoCoupler-4p-ACEC"))
    )
    (comp (ref "U6")
      (value "PS2501AL-1-F3-A")
      (footprint "SOP254P960X380-4N")
      (description "Optocoupler 1ch, Vceo=70V, Ic=30mA, CTR=200-400% @ 5mA")
      (fields
        (field (name "MANUFACTURER") "CEL")
        (field (name "AUTHOR") "EB")
        (field (name "CHECKED BY") "Unchecked")
      )
      (libsource (lib "TC_Parts") (part "OptoCoupler-4p-ACEC"))
    )
    (comp (ref "U7")
      (value "OPA210IDT")
      (footprint "SOIC127P600X175-8N")
      (description "UltraLow Noise-drift, high precision, Low-Power, 36-V")
      (fields
        (field (name "MANUFACTURER") "Analog Devices")
        (field (name "AUTHOR") "EB")
        (field (name "CHECKED BY") "Unchecked")
      )
      (libsource (lib "TC_Parts") (part "OPA210IDT"))
    )
    (comp (ref "U8")
      (value "OPA210IDT")
      (footprint "SOIC127P600X175-8N")
      (description "UltraLow Noise-drift, high precision, Low-Power, 36-V")
      (fields
        (field (name "MANUFACTURER") "Analog Devices")
        (field (name "AUTHOR") "EB")
        (field (name "CHECKED BY") "Unchecked")
      )
      (libsource (lib "TC_Parts") (part "OPA210IDT"))
    )
    (comp (ref "U9")
      (value "MC7915ACTG")
      (footprint "TO220-3_FLAT")
      (description "Linear Voltage Regulator,Negative, Fixed, -35V In, -15V And -1A Out")
      (fields
        (field (name "MANUFACTURER") "OnSEMI")
        (field (name "AUTHOR") "EB")
        (field (name "CHECKED BY") "Unchecked")
      )
      (libsource (lib "TC_Parts") (part "LDO_GIO"))
    )
    (comp (ref "U10")
      (value "OPA210IDT")
      (footprint "SOIC127P600X175-8N")
      (description "UltraLow Noise-drift, high precision, Low-Power, 36-V")
      (fields
        (field (name "MANUFACTURER") "Analog Devices")
        (field (name "AUTHOR") "EB")
        (field (name "CHECKED BY") "Unchecked")
      )
      (libsource (lib "TC_Parts") (part "OPA210IDT"))
    )
    (comp (ref "U11")
      (value "OPA210IDT")
      (footprint "SOIC127P600X175-8N")
      (description "UltraLow Noise-drift, high precision, Low-Power, 36-V")
      (fields
        (field (name "MANUFACTURER") "Analog Devices")
        (field (name "AUTHOR") "EB")
        (field (name "CHECKED BY") "Unchecked")
      )
      (libsource (lib "TC_Parts") (part "OPA210IDT"))
    )
    (comp (ref "U12")
      (value "OPA210IDT")
      (footprint "SOIC127P600X175-8N")
      (description "UltraLow Noise-drift, high precision, Low-Power, 36-V")
      (fields
        (field (name "MANUFACTURER") "Analog Devices")
        (field (name "AUTHOR") "EB")
        (field (name "CHECKED BY") "Unchecked")
      )
      (libsource (lib "TC_Parts") (part "OPA210IDT"))
    )
    (comp (ref "U13")
      (value "OPA210IDT")
      (footprint "SOIC127P600X175-8N")
      (description "UltraLow Noise-drift, high precision, Low-Power, 36-V")
      (fields
        (field (name "MANUFACTURER") "Analog Devices")
        (field (name "AUTHOR") "EB")
        (field (name "CHECKED BY") "Unchecked")
      )
      (libsource (lib "TC_Parts") (part "OPA210IDT"))
    )
    (comp (ref "U14")
      (value "SN74HC688PWR2")
      (footprint "SOIC127P1030X265-20N")
      (description "8-Bit Identity Comparators")
      (fields
        (field (name "MANUFACTURER") "Texas Instruments")
        (field (name "AUTHOR") "EB")
        (field (name "CHECKED BY") "Unchecked")
      )
      (libsource (lib "TC_Parts") (part "74HCT688"))
    )
    (comp (ref "U15")
      (value "OPA210IDT")
      (footprint "SOIC127P600X175-8N")
      (description "UltraLow Noise-drift, high precision, Low-Power, 36-V")
      (fields
        (field (name "MANUFACTURER") "Analog Devices")
        (field (name "AUTHOR") "EB")
        (field (name "CHECKED BY") "Unchecked")
      )
      (libsource (lib "TC_Parts") (part "OPA210IDT"))
    )
    (comp (ref "U16")
      (value "OPA210IDT")
      (footprint "SOIC127P600X175-8N")
      (description "UltraLow Noise-drift, high precision, Low-Power, 36-V")
      (fields
        (field (name "MANUFACTURER") "Analog Devices")
        (field (name "AUTHOR") "EB")
        (field (name "CHECKED BY") "Unchecked")
      )
      (libsource (lib "TC_Parts") (part "OPA210IDT"))
    )
    (comp (ref "U17")
      (value "DAC8728SPAG")
      (footprint "TSQFP50P1200X1200X105-64N")
      (description "Octal, 16-Bit, Low-Power, High-Voltage Output, Parallel Input DAC")
      (fields
        (field (name "MANUFACTURER") "Texas Instruments")
        (field (name "AUTHOR") "EB")
        (field (name "CHECKED BY") "Unchecked")
      )
      (libsource (lib "TC_Parts") (part "DAC8728SPAG"))
    )
  )
  (nets
    (net (code "1") (name "+5V") (class "Default")
      (node (ref "C22") (pin "1") (pinfunction "1_1") (pintype "passive"))
      (node (ref "C27") (pin "1") (pinfunction "1_1") (pintype "passive"))
      (node (ref "C36") (pin "P") (pinfunction "P_P") (pintype "passive"))
      (node (ref "C49") (pin "1") (pinfunction "1_1") (pintype "passive"))
      (node (ref "C58") (pin "1") (pinfunction "1_1") (pintype "passive"))
      (node (ref "C59") (pin "2") (pinfunction "2_2") (pintype "passive"))
      (node (ref "P10") (pin "A10") (pinfunction "A10_A10") (pintype "passive"))
      (node (ref "P10") (pin "A11") (pinfunction "A11_A11") (pintype "passive"))
      (node (ref "P10") (pin "A12") (pinfunction "A12_A12") (pintype "passive"))
      (node (ref "P10") (pin "A13") (pinfunction "A13_A13") (pintype "passive"))
      (node (ref "P10") (pin "A14") (pinfunction "A14_A14") (pintype "passive"))
      (node (ref "P10") (pin "A15") (pinfunction "A15_A15") (pintype "passive"))
      (node (ref "P10") (pin "A16") (pinfunction "A16_A16") (pintype "passive"))
      (node (ref "P10") (pin "A17") (pinfunction "A17_A17") (pintype "passive"))
      (node (ref "P10") (pin "A18") (pinfunction "A18_A18") (pintype "passive"))
      (node (ref "P10") (pin "A19") (pinfunction "A19_A19") (pintype "passive"))
      (node (ref "P10") (pin "A20") (pinfunction "A20_A20") (pintype "passive"))
      (node (ref "P10") (pin "A9") (pinfunction "A9_A9") (pintype "passive"))
      (node (ref "R51") (pin "1") (pinfunction "1_1") (pintype "passive"))
      (node (ref "R59") (pin "1") (pinfunction "1_1") (pintype "passive"))
      (node (ref "R64") (pin "2") (pinfunction "2_2") (pintype "passive"))
      (node (ref "R8") (pin "2") (pinfunction "2_2") (pintype "passive"))
      (node (ref "S1") (pin "1") (pinfunction "1a_1") (pintype "passive"))
      (node (ref "S1") (pin "2") (pinfunction "2a_2") (pintype "passive"))
      (node (ref "S1") (pin "3") (pinfunction "3a_3") (pintype "passive"))
      (node (ref "S1") (pin "4") (pinfunction "4a_4") (pintype "passive"))
      (node (ref "S1") (pin "5") (pinfunction "5a_5") (pintype "passive"))
      (node (ref "T5") (pin "4") (pinfunction "S_4") (pintype "passive"))
      (node (ref "U14") (pin "20") (pinfunction "VCC_20") (pintype "power_in"))
      (node (ref "U14") (pin "3") (pinfunction "Q0_3") (pintype "input"))
      (node (ref "U17") (pin "24") (pinfunction "DVdd_24") (pintype "passive"))
      (node (ref "U17") (pin "55") (pinfunction "IOVdd_55") (pintype "passive"))
      (node (ref "U17") (pin "56") (pinfunction "DVdd_56") (pintype "passive"))
      (node (ref "U5") (pin "1") (pinfunction "1_1") (pintype "passive"))
      (node (ref "U6") (pin "1") (pinfunction "1_1") (pintype "passive"))
    )
    (net (code "2") (name "+15V") (class "Default")
      (node (ref "C4") (pin "1") (pinfunction "1_1") (pintype "passive"))
      (node (ref "D1") (pin "1") (pinfunction "1_1") (pintype "passive"))
      (node (ref "R1") (pin "2") (pinfunction "2_2") (pintype "passive"))
      (node (ref "R15") (pin "1") (pinfunction "1_1") (pintype "passive"))
      (node (ref "R16") (pin "1") (pinfunction "1_1") (pintype "passive"))
      (node (ref "R19") (pin "2") (pinfunction "2_2") (pintype "passive"))
      (node (ref "R25") (pin "1") (pinfunction "1_1") (pintype "passive"))
      (node (ref "R26") (pin "1") (pinfunction "1_1") (pintype "passive"))
      (node (ref "R3") (pin "2") (pinfunction "2_2") (pintype "passive"))
      (node (ref "R34") (pin "1") (pinfunction "1_1") (pintype "passive"))
      (node (ref "R35") (pin "1") (pinfunction "1_1") (pintype "passive"))
      (node (ref "R42") (pin "1") (pinfunction "1_1") (pintype "passive"))
      (node (ref "R43") (pin "1") (pinfunction "1_1") (pintype "passive"))
      (node (ref "U1") (pin "3") (pinfunction "Out_3") (pintype "passive"))
    )
    (net (code "3") (name "+15V_ICref") (class "Default")
      (node (ref "C1") (pin "1") (pinfunction "1_1") (pintype "passive"))
      (node (ref "C2") (pin "1") (pinfunction "1_1") (pintype "passive"))
      (node (ref "C3") (pin "1") (pinfunction "1_1") (pintype "passive"))
      (node (ref "C7") (pin "2") (pinfunction "2_2") (pintype "passive"))
      (node (ref "R1") (pin "1") (pinfunction "1_1") (pintype "passive"))
      (node (ref "T2") (pin "4") (pinfunction "S_4") (pintype "passive"))
      (node (ref "U3") (pin "7") (pinfunction "V+_7") (pintype "passive"))
      (node (ref "U4") (pin "7") (pinfunction "V+_7") (pintype "passive"))
    )
    (net (code "4") (name "-15V") (class "Default")
      (node (ref "C12") (pin "2") (pinfunction "2_2") (pintype "passive"))
      (node (ref "R11") (pin "1") (pinfunction "1_1") (pintype "passive"))
      (node (ref "R20") (pin "2") (pinfunction "2_2") (pintype "passive"))
      (node (ref "R22") (pin "1") (pinfunction "1_1") (pintype "passive"))
      (node (ref "R24") (pin "1") (pinfunction "1_1") (pintype "passive"))
      (node (ref "R31") (pin "1") (pinfunction "1_1") (pintype "passive"))
      (node (ref "R33") (pin "1") (pinfunction "1_1") (pintype "passive"))
      (node (ref "R39") (pin "1") (pinfunction "1_1") (pintype "passive"))
      (node (ref "R41") (pin "1") (pinfunction "1_1") (pintype "passive"))
      (node (ref "R48") (pin "1") (pinfunction "1_1") (pintype "passive"))
      (node (ref "R49") (pin "1") (pinfunction "1_1") (pintype "passive"))
      (node (ref "R65") (pin "1") (pinfunction "1_1") (pintype "passive"))
      (node (ref "U9") (pin "3") (pinfunction "Out_3") (pintype "passive"))
    )
    (net (code "5") (name "/+18V") (class "Default")
      (node (ref "C5") (pin "P") (pinfunction "P_P") (pintype "passive"))
      (node (ref "C6") (pin "1") (pinfunction "1_1") (pintype "passive"))
      (node (ref "P10") (pin "A5") (pinfunction "A5_A5") (pintype "passive"))
      (node (ref "P10") (pin "A6") (pinfunction "A6_A6") (pintype "passive"))
      (node (ref "P10") (pin "C5") (pinfunction "C5_C5") (pintype "passive"))
      (node (ref "P10") (pin "C6") (pinfunction "C6_C6") (pintype "passive"))
      (node (ref "R2") (pin "1") (pinfunction "1_1") (pintype "passive"))
      (node (ref "T1") (pin "4") (pinfunction "S_4") (pintype "passive"))
    )
    (net (code "6") (name "/+28V") (class "Default")
      (node (ref "P10") (pin "A7") (pinfunction "A7_A7") (pintype "passive"))
      (node (ref "P10") (pin "A8") (pinfunction "A8_A8") (pintype "passive"))
      (node (ref "P10") (pin "C8") (pinfunction "C8_C8") (pintype "passive"))
    )
    (net (code "7") (name "/-18V") (class "Default")
      (node (ref "C13") (pin "N") (pinfunction "N_N") (pintype "passive"))
      (node (ref "C15") (pin "2") (pinfunction "2_2") (pintype "passive"))
      (node (ref "P10") (pin "A2") (pinfunction "A2_A2") (pintype "passive"))
      (node (ref "P10") (pin "C2") (pinfunction "C2_C2") (pintype "passive"))
      (node (ref "R14") (pin "1") (pinfunction "1_1") (pintype "passive"))
      (node (ref "T4") (pin "2") (pinfunction "S_2") (pintype "passive"))
    )
    (net (code "8") (name "/A0") (class "Default")
      (node (ref "P10") (pin "C25") (pinfunction "C25_C25") (pintype "passive"))
      (node (ref "P9") (pin "33") (pinfunction "33_33") (pintype "passive"))
      (node (ref "U17") (pin "20") (pinfunction "A0_20") (pintype "input"))
    )
    (net (code "9") (name "/A1") (class "Default")
      (node (ref "P10") (pin "C26") (pinfunction "C26_C26") (pintype "passive"))
      (node (ref "P9") (pin "35") (pinfunction "35_35") (pintype "passive"))
      (node (ref "U17") (pin "21") (pinfunction "A1_21") (pintype "input"))
    )
    (net (code "10") (name "/A2") (class "Default")
      (node (ref "P10") (pin "C27") (pinfunction "C27_C27") (pintype "passive"))
      (node (ref "P9") (pin "37") (pinfunction "37_37") (pintype "passive"))
      (node (ref "U17") (pin "26") (pinfunction "A2_26") (pintype "input"))
    )
    (net (code "11") (name "/A3") (class "Default")
      (node (ref "P10") (pin "C28") (pinfunction "C28_C28") (pintype "passive"))
      (node (ref "P9") (pin "39") (pinfunction "39_39") (pintype "passive"))
      (node (ref "U14") (pin "17") (pinfunction "P7_17") (pintype "input"))
    )
    (net (code "12") (name "/A4") (class "Default")
      (node (ref "P10") (pin "C29") (pinfunction "C29_C29") (pintype "passive"))
      (node (ref "P9") (pin "41") (pinfunction "41_41") (pintype "passive"))
      (node (ref "U14") (pin "15") (pinfunction "P6_15") (pintype "input"))
    )
    (net (code "13") (name "/A5") (class "Default")
      (node (ref "P10") (pin "C30") (pinfunction "C30_C30") (pintype "passive"))
      (node (ref "P9") (pin "43") (pinfunction "43_43") (pintype "passive"))
      (node (ref "U14") (pin "13") (pinfunction "P5_13") (pintype "input"))
    )
    (net (code "14") (name "/A6") (class "Default")
      (node (ref "P10") (pin "C31") (pinfunction "C31_C31") (pintype "passive"))
      (node (ref "P9") (pin "45") (pinfunction "45_45") (pintype "passive"))
      (node (ref "U14") (pin "11") (pinfunction "P4_11") (pintype "input"))
    )
    (net (code "15") (name "/A7") (class "Default")
      (node (ref "P10") (pin "C32") (pinfunction "C32_C32") (pintype "passive"))
      (node (ref "P9") (pin "47") (pinfunction "47_47") (pintype "passive"))
      (node (ref "U14") (pin "8") (pinfunction "P3_8") (pintype "input"))
    )
    (net (code "16") (name "/D1") (class "Default")
      (node (ref "P10") (pin "C9") (pinfunction "C9_C9") (pintype "passive"))
      (node (ref "P9") (pin "1") (pinfunction "1_1") (pintype "passive"))
      (node (ref "U17") (pin "46") (pinfunction "D0_46") (pintype "bidirectional"))
    )
    (net (code "17") (name "/D2") (class "Default")
      (node (ref "P10") (pin "C10") (pinfunction "C10_C10") (pintype "passive"))
      (node (ref "P9") (pin "3") (pinfunction "3_3") (pintype "passive"))
      (node (ref "U17") (pin "47") (pinfunction "D1_47") (pintype "bidirectional"))
    )
    (net (code "18") (name "/D3") (class "Default")
      (node (ref "P10") (pin "C11") (pinfunction "C11_C11") (pintype "passive"))
      (node (ref "P9") (pin "5") (pinfunction "5_5") (pintype "passive"))
      (node (ref "U17") (pin "48") (pinfunction "D2_48") (pintype "bidirectional"))
    )
    (net (code "19") (name "/D4") (class "Default")
      (node (ref "P10") (pin "C12") (pinfunction "C12_C12") (pintype "passive"))
      (node (ref "P9") (pin "7") (pinfunction "7_7") (pintype "passive"))
      (node (ref "U17") (pin "49") (pinfunction "D3_49") (pintype "bidirectional"))
    )
    (net (code "20") (name "/D5") (class "Default")
      (node (ref "P10") (pin "C13") (pinfunction "C13_C13") (pintype "passive"))
      (node (ref "P9") (pin "9") (pinfunction "9_9") (pintype "passive"))
      (node (ref "U17") (pin "50") (pinfunction "D4_50") (pintype "bidirectional"))
    )
    (net (code "21") (name "/D6") (class "Default")
      (node (ref "P10") (pin "C14") (pinfunction "C14_C14") (pintype "passive"))
      (node (ref "P9") (pin "11") (pinfunction "11_11") (pintype "passive"))
      (node (ref "U17") (pin "51") (pinfunction "D5_51") (pintype "bidirectional"))
    )
    (net (code "22") (name "/D7") (class "Default")
      (node (ref "P10") (pin "C15") (pinfunction "C15_C15") (pintype "passive"))
      (node (ref "P9") (pin "13") (pinfunction "13_13") (pintype "passive"))
      (node (ref "U17") (pin "52") (pinfunction "D6_52") (pintype "bidirectional"))
    )
    (net (code "23") (name "/D8") (class "Default")
      (node (ref "P10") (pin "C16") (pinfunction "C16_C16") (pintype "passive"))
      (node (ref "P9") (pin "15") (pinfunction "15_15") (pintype "passive"))
      (node (ref "U17") (pin "59") (pinfunction "D7_59") (pintype "bidirectional"))
    )
    (net (code "24") (name "/D9") (class "Default")
      (node (ref "P10") (pin "C17") (pinfunction "C17_C17") (pintype "passive"))
      (node (ref "P9") (pin "17") (pinfunction "17_17") (pintype "passive"))
      (node (ref "U17") (pin "60") (pinfunction "D8_60") (pintype "bidirectional"))
    )
    (net (code "25") (name "/D10") (class "Default")
      (node (ref "P10") (pin "C18") (pinfunction "C18_C18") (pintype "passive"))
      (node (ref "P9") (pin "19") (pinfunction "19_19") (pintype "passive"))
      (node (ref "U17") (pin "61") (pinfunction "D9_61") (pintype "bidirectional"))
    )
    (net (code "26") (name "/D11") (class "Default")
      (node (ref "P10") (pin "C19") (pinfunction "C19_C19") (pintype "passive"))
      (node (ref "P9") (pin "21") (pinfunction "21_21") (pintype "passive"))
      (node (ref "U17") (pin "62") (pinfunction "D10_62") (pintype "bidirectional"))
    )
    (net (code "27") (name "/D12") (class "Default")
      (node (ref "P10") (pin "C20") (pinfunction "C20_C20") (pintype "passive"))
      (node (ref "P9") (pin "23") (pinfunction "23_23") (pintype "passive"))
      (node (ref "U17") (pin "63") (pinfunction "D11_63") (pintype "bidirectional"))
    )
    (net (code "28") (name "/D13") (class "Default")
      (node (ref "P10") (pin "C21") (pinfunction "C21_C21") (pintype "passive"))
      (node (ref "P9") (pin "25") (pinfunction "25_25") (pintype "passive"))
      (node (ref "U17") (pin "64") (pinfunction "D12_64") (pintype "bidirectional"))
    )
    (net (code "29") (name "/D14") (class "Default")
      (node (ref "P10") (pin "C22") (pinfunction "C22_C22") (pintype "passive"))
      (node (ref "P9") (pin "27") (pinfunction "27_27") (pintype "passive"))
      (node (ref "U17") (pin "1") (pinfunction "D13_1") (pintype "bidirectional"))
    )
    (net (code "30") (name "/D15") (class "Default")
      (node (ref "P10") (pin "C23") (pinfunction "C23_C23") (pintype "passive"))
      (node (ref "P9") (pin "29") (pinfunction "29_29") (pintype "passive"))
      (node (ref "U17") (pin "2") (pinfunction "D14_2") (pintype "bidirectional"))
    )
    (net (code "31") (name "/D16") (class "Default")
      (node (ref "P10") (pin "C24") (pinfunction "C24_C24") (pintype "passive"))
      (node (ref "P9") (pin "31") (pinfunction "31_31") (pintype "passive"))
      (node (ref "U17") (pin "3") (pinfunction "D15_3") (pintype "bidirectional"))
    )
    (net (code "32") (name "/DIRECT") (class "Default")
      (node (ref "P10") (pin "C7") (pinfunction "C7_C7") (pintype "passive+no_connect"))
    )
    (net (code "33") (name "/STROBE") (class "Default")
      (node (ref "P10") (pin "C1") (pinfunction "C1_C1") (pintype "passive"))
      (node (ref "P9") (pin "49") (pinfunction "49_49") (pintype "passive"))
      (node (ref "U14") (pin "2") (pinfunction "P0_2") (pintype "input"))
    )
    (net (code "34") (name "/SYNC") (class "Default")
      (node (ref "P10") (pin "A1") (pinfunction "A1_A1") (pintype "passive+no_connect"))
    )
    (net (code "35") (name "/Vout-0") (class "Default")
      (node (ref "R17") (pin "1") (pinfunction "1_1") (pintype "passive"))
      (node (ref "U17") (pin "13") (pinfunction "Vout-0_13") (pintype "passive"))
    )
    (net (code "36") (name "/Vout-1") (class "Default")
      (node (ref "R18") (pin "1") (pinfunction "1_1") (pintype "passive"))
      (node (ref "U17") (pin "10") (pinfunction "Vout-1_10") (pintype "passive"))
    )
    (net (code "37") (name "/Vout-2") (class "Default")
      (node (ref "R28") (pin "1") (pinfunction "1_1") (pintype "passive"))
      (node (ref "U17") (pin "7") (pinfunction "Vout-2_7") (pintype "passive"))
    )
    (net (code "38") (name "/Vout-3") (class "Default")
      (node (ref "R29") (pin "1") (pinfunction "1_1") (pintype "passive"))
      (node (ref "U17") (pin "5") (pinfunction "Vout-3_5") (pintype "passive"))
    )
    (net (code "39") (name "/Vout-4") (class "Default")
      (node (ref "R36") (pin "1") (pinfunction "1_1") (pintype "passive"))
      (node (ref "U17") (pin "44") (pinfunction "Vout-4_44") (pintype "passive"))
    )
    (net (code "40") (name "/Vout-5") (class "Default")
      (node (ref "R37") (pin "1") (pinfunction "1_1") (pintype "passive"))
      (node (ref "U17") (pin "42") (pinfunction "Vout-5_42") (pintype "passive"))
    )
    (net (code "41") (name "/Vout-6") (class "Default")
      (node (ref "R46") (pin "1") (pinfunction "1_1") (pintype "passive"))
      (node (ref "U17") (pin "39") (pinfunction "Vout-6_39") (pintype "passive"))
    )
    (net (code "42") (name "/Vout-7") (class "Default")
      (node (ref "R47") (pin "1") (pinfunction "1_1") (pintype "passive"))
      (node (ref "U17") (pin "36") (pinfunction "Vout-7_36") (pintype "passive"))
    )
    (net (code "43") (name "/Vref+1.666V") (class "Default")
      (node (ref "J1") (pin "3") (pinfunction "3_3") (pintype "passive"))
      (node (ref "J2") (pin "3") (pinfunction "3_3") (pintype "passive"))
      (node (ref "R6") (pin "2") (pinfunction "2_2") (pintype "passive"))
      (node (ref "U3") (pin "2") (pinfunction "-_2") (pintype "passive"))
      (node (ref "U3") (pin "5") (pinfunction "Sense_5") (pintype "passive"))
      (node (ref "U3") (pin "6") (pinfunction "OUT_6") (pintype "passive"))
    )
    (net (code "44") (name "/Vref+3.333V") (class "Default")
      (node (ref "J1") (pin "1") (pinfunction "1_1") (pintype "passive"))
      (node (ref "J2") (pin "1") (pinfunction "1_1") (pintype "passive"))
      (node (ref "R7") (pin "2") (pinfunction "2_2") (pintype "passive"))
      (node (ref "U4") (pin "2") (pinfunction "-_2") (pintype "passive"))
      (node (ref "U4") (pin "5") (pinfunction "Sense_5") (pintype "passive"))
      (node (ref "U4") (pin "6") (pinfunction "OUT_6") (pintype "passive"))
    )
    (net (code "45") (name "/Vref+5V") (class "Default")
      (node (ref "R50") (pin "2") (pinfunction "2_2") (pintype "passive"))
      (node (ref "U3") (pin "3") (pinfunction "+_3") (pintype "passive"))
      (node (ref "U4") (pin "1") (pinfunction "Ref_1") (pintype "passive"))
    )
    (net (code "46") (name "AGND") (class "Default")
      (node (ref "C1") (pin "2") (pinfunction "2_2") (pintype "passive"))
      (node (ref "C11") (pin "2") (pinfunction "2_2") (pintype "passive"))
      (node (ref "C12") (pin "1") (pinfunction "1_1") (pintype "passive"))
      (node (ref "C13") (pin "P") (pinfunction "P_P") (pintype "passive"))
      (node (ref "C15") (pin "1") (pinfunction "1_1") (pintype "passive"))
      (node (ref "C16") (pin "2") (pinfunction "2_2") (pintype "passive"))
      (node (ref "C17") (pin "2") (pinfunction "2_2") (pintype "passive"))
      (node (ref "C18") (pin "2") (pinfunction "2_2") (pintype "passive"))
      (node (ref "C19") (pin "2") (pinfunction "2_2") (pintype "passive"))
      (node (ref "C2") (pin "2") (pinfunction "2_2") (pintype "passive"))
      (node (ref "C20") (pin "2") (pinfunction "2_2") (pintype "passive"))
      (node (ref "C21") (pin "2") (pinfunction "2_2") (pintype "passive"))
      (node (ref "C23") (pin "2") (pinfunction "2_2") (pintype "passive"))
      (node (ref "C24") (pin "2") (pinfunction "2_2") (pintype "passive"))
      (node (ref "C25") (pin "2") (pinfunction "2_2") (pintype "passive"))
      (node (ref "C26") (pin "1") (pinfunction "1_1") (pintype "passive"))
      (node (ref "C29") (pin "1") (pinfunction "1_1") (pintype "passive"))
      (node (ref "C30") (pin "2") (pinfunction "2_2") (pintype "passive"))
      (node (ref "C31") (pin "2") (pinfunction "2_2") (pintype "passive"))
      (node (ref "C32") (pin "2") (pinfunction "2_2") (pintype "passive"))
      (node (ref "C33") (pin "2") (pinfunction "2_2") (pintype "passive"))
      (node (ref "C34") (pin "2") (pinfunction "2_2") (pintype "passive"))
      (node (ref "C35") (pin "2") (pinfunction "2_2") (pintype "passive"))
      (node (ref "C37") (pin "2") (pinfunction "2_2") (pintype "passive"))
      (node (ref "C38") (pin "2") (pinfunction "2_2") (pintype "passive"))
      (node (ref "C39") (pin "2") (pinfunction "2_2") (pintype "passive"))
      (node (ref "C4") (pin "2") (pinfunction "2_2") (pintype "passive"))
      (node (ref "C40") (pin "2") (pinfunction "2_2") (pintype "passive"))
      (node (ref "C41") (pin "2") (pinfunction "2_2") (pintype "passive"))
      (node (ref "C42") (pin "2") (pinfunction "2_2") (pintype "passive"))
      (node (ref "C43") (pin "2") (pinfunction "2_2") (pintype "passive"))
      (node (ref "C44") (pin "2") (pinfunction "2_2") (pintype "passive"))
      (node (ref "C45") (pin "2") (pinfunction "2_2") (pintype "passive"))
      (node (ref "C46") (pin "2") (pinfunction "2_2") (pintype "passive"))
      (node (ref "C47") (pin "2") (pinfunction "2_2") (pintype "passive"))
      (node (ref "C48") (pin "2") (pinfunction "2_2") (pintype "passive"))
      (node (ref "C5") (pin "N") (pinfunction "N_N") (pintype "passive"))
      (node (ref "C50") (pin "2") (pinfunction "2_2") (pintype "passive"))
      (node (ref "C51") (pin "2") (pinfunction "2_2") (pintype "passive"))
      (node (ref "C52") (pin "2") (pinfunction "2_2") (pintype "passive"))
      (node (ref "C53") (pin "2") (pinfunction "2_2") (pintype "passive"))
      (node (ref "C54") (pin "2") (pinfunction "2_2") (pintype "passive"))
      (node (ref "C55") (pin "2") (pinfunction "2_2") (pintype "passive"))
      (node (ref "C56") (pin "2") (pinfunction "2_2") (pintype "passive"))
      (node (ref "C57") (pin "2") (pinfunction "2_2") (pintype "passive"))
      (node (ref "C6") (pin "2") (pinfunction "2_2") (pintype "passive"))
      (node (ref "C7") (pin "1") (pinfunction "1_1") (pintype "passive"))
      (node (ref "C8") (pin "2") (pinfunction "2_2") (pintype "passive"))
      (node (ref "C9") (pin "2") (pinfunction "2_2") (pintype "passive"))
      (node (ref "D1") (pin "2") (pinfunction "2_2") (pintype "passive"))
      (node (ref "D2") (pin "1") (pinfunction "1_1") (pintype "passive"))
      (node (ref "P1") (pin "2") (pinfunction "2_2") (pintype "passive"))
      (node (ref "P10") (pin "A3") (pinfunction "A3_A3") (pintype "passive"))
      (node (ref "P10") (pin "A4") (pinfunction "A4_A4") (pintype "passive"))
      (node (ref "P10") (pin "C3") (pinfunction "C3_C3") (pintype "passive"))
      (node (ref "P10") (pin "C4") (pinfunction "C4_C4") (pintype "passive"))
      (node (ref "P2") (pin "2") (pinfunction "2_2") (pintype "passive"))
      (node (ref "P3") (pin "2") (pinfunction "2_2") (pintype "passive"))
      (node (ref "P4") (pin "2") (pinfunction "2_2") (pintype "passive"))
      (node (ref "P5") (pin "2") (pinfunction "2_2") (pintype "passive"))
      (node (ref "P6") (pin "2") (pinfunction "2_2") (pintype "passive"))
      (node (ref "P7") (pin "2") (pinfunction "2_2") (pintype "passive"))
      (node (ref "P8") (pin "2") (pinfunction "2_2") (pintype "passive"))
      (node (ref "R10") (pin "1") (pinfunction "1_1") (pintype "passive"))
      (node (ref "R11") (pin "2") (pinfunction "2_2") (pintype "passive"))
      (node (ref "R5") (pin "1") (pinfunction "1_1") (pintype "passive"))
      (node (ref "R6") (pin "1") (pinfunction "1_1") (pintype "passive"))
      (node (ref "R65") (pin "2") (pinfunction "2_2") (pintype "passive"))
      (node (ref "R7") (pin "1") (pinfunction "1_1") (pintype "passive"))
      (node (ref "U1") (pin "2") (pinfunction "GND_2") (pintype "passive"))
      (node (ref "U17") (pin "40") (pinfunction "AGND-B_40") (pintype "passive"))
      (node (ref "U17") (pin "9") (pinfunction "AGND-A_9") (pintype "passive"))
      (node (ref "U2") (pin "3") (pinfunction "Gnd_3") (pintype "passive"))
      (node (ref "U2") (pin "4") (pinfunction "Gnd_sns_4") (pintype "passive"))
      (node (ref "U3") (pin "1") (pinfunction "Ref_1") (pintype "passive"))
      (node (ref "U3") (pin "4") (pinfunction "V-_4") (pintype "passive"))
      (node (ref "U4") (pin "3") (pinfunction "+_3") (pintype "passive"))
      (node (ref "U4") (pin "4") (pinfunction "V-_4") (pintype "passive"))
      (node (ref "U5") (pin "3") (pinfunction "3_3") (pintype "passive"))
      (node (ref "U6") (pin "4") (pinfunction "4_4") (pintype "passive"))
      (node (ref "U9") (pin "1") (pinfunction "GND_1") (pintype "passive"))
    )
    (net (code "47") (name "DGND") (class "Default")
      (node (ref "C14") (pin "2") (pinfunction "2_2") (pintype "passive"))
      (node (ref "C22") (pin "2") (pinfunction "2_2") (pintype "passive"))
      (node (ref "C27") (pin "2") (pinfunction "2_2") (pintype "passive"))
      (node (ref "C36") (pin "N") (pinfunction "N_N") (pintype "passive"))
      (node (ref "C58") (pin "2") (pinfunction "2_2") (pintype "passive"))
      (node (ref "C59") (pin "1") (pinfunction "1_1") (pintype "passive"))
      (node (ref "P10") (pin "A21") (pinfunction "A21_A21") (pintype "passive"))
      (node (ref "P10") (pin "A22") (pinfunction "A22_A22") (pintype "passive"))
      (node (ref "P10") (pin "A23") (pinfunction "A23_A23") (pintype "passive"))
      (node (ref "P10") (pin "A24") (pinfunction "A24_A24") (pintype "passive"))
      (node (ref "P10") (pin "A25") (pinfunction "A25_A25") (pintype "passive"))
      (node (ref "P10") (pin "A26") (pinfunction "A26_A26") (pintype "passive"))
      (node (ref "P10") (pin "A27") (pinfunction "A27_A27") (pintype "passive"))
      (node (ref "P10") (pin "A28") (pinfunction "A28_A28") (pintype "passive"))
      (node (ref "P10") (pin "A29") (pinfunction "A29_A29") (pintype "passive"))
      (node (ref "P10") (pin "A30") (pinfunction "A30_A30") (pintype "passive"))
      (node (ref "P10") (pin "A31") (pinfunction "A31_A31") (pintype "passive"))
      (node (ref "P10") (pin "A32") (pinfunction "A32_A32") (pintype "passive"))
      (node (ref "P9") (pin "10") (pinfunction "10_10") (pintype "passive"))
      (node (ref "P9") (pin "12") (pinfunction "12_12") (pintype "passive"))
      (node (ref "P9") (pin "14") (pinfunction "14_14") (pintype "passive"))
      (node (ref "P9") (pin "16") (pinfunction "16_16") (pintype "passive"))
      (node (ref "P9") (pin "18") (pinfunction "18_18") (pintype "passive"))
      (node (ref "P9") (pin "2") (pinfunction "2_2") (pintype "passive"))
      (node (ref "P9") (pin "20") (pinfunction "20_20") (pintype "passive"))
      (node (ref "P9") (pin "22") (pinfunction "22_22") (pintype "passive"))
      (node (ref "P9") (pin "24") (pinfunction "24_24") (pintype "passive"))
      (node (ref "P9") (pin "26") (pinfunction "26_26") (pintype "passive"))
      (node (ref "P9") (pin "28") (pinfunction "28_28") (pintype "passive"))
      (node (ref "P9") (pin "30") (pinfunction "30_30") (pintype "passive"))
      (node (ref "P9") (pin "32") (pinfunction "32_32") (pintype "passive"))
      (node (ref "P9") (pin "34") (pinfunction "34_34") (pintype "passive"))
      (node (ref "P9") (pin "36") (pinfunction "36_36") (pintype "passive"))
      (node (ref "P9") (pin "38") (pinfunction "38_38") (pintype "passive"))
      (node (ref "P9") (pin "4") (pinfunction "4_4") (pintype "passive"))
      (node (ref "P9") (pin "40") (pinfunction "40_40") (pintype "passive"))
      (node (ref "P9") (pin "42") (pinfunction "42_42") (pintype "passive"))
      (node (ref "P9") (pin "44") (pinfunction "44_44") (pintype "passive"))
      (node (ref "P9") (pin "46") (pinfunction "46_46") (pintype "passive"))
      (node (ref "P9") (pin "48") (pinfunction "48_48") (pintype "passive"))
      (node (ref "P9") (pin "50") (pinfunction "50_50") (pintype "passive"))
      (node (ref "P9") (pin "6") (pinfunction "6_6") (pintype "passive"))
      (node (ref "P9") (pin "8") (pinfunction "8_8") (pintype "passive"))
      (node (ref "R44") (pin "1") (pinfunction "1_1") (pintype "passive"))
      (node (ref "R45") (pin "1") (pinfunction "1_1") (pintype "passive"))
      (node (ref "R52") (pin "1") (pinfunction "1_1") (pintype "passive"))
      (node (ref "R53") (pin "1") (pinfunction "1_1") (pintype "passive"))
      (node (ref "R54") (pin "1") (pinfunction "1_1") (pintype "passive"))
      (node (ref "R55") (pin "1") (pinfunction "1_1") (pintype "passive"))
      (node (ref "R56") (pin "1") (pinfunction "1_1") (pintype "passive"))
      (node (ref "R57") (pin "1") (pinfunction "1_1") (pintype "passive"))
      (node (ref "R58") (pin "1") (pinfunction "1_1") (pintype "passive"))
      (node (ref "R60") (pin "1") (pinfunction "1_1") (pintype "passive"))
      (node (ref "R61") (pin "1") (pinfunction "1_1") (pintype "passive"))
      (node (ref "R63") (pin "2") (pinfunction "2_2") (pintype "passive"))
      (node (ref "T3") (pin "2") (pinfunction "S_2") (pintype "passive"))
      (node (ref "U14") (pin "1") (pinfunction "~{OE}_1") (pintype "input"))
      (node (ref "U14") (pin "10") (pinfunction "GND_10") (pintype "power_in"))
      (node (ref "U14") (pin "4") (pinfunction "P1_4") (pintype "input"))
      (node (ref "U14") (pin "5") (pinfunction "Q1_5") (pintype "input"))
      (node (ref "U14") (pin "6") (pinfunction "P2_6") (pintype "input"))
      (node (ref "U14") (pin "7") (pinfunction "Q2_7") (pintype "input"))
      (node (ref "U17") (pin "25") (pinfunction "DGND_25") (pintype "passive"))
      (node (ref "U17") (pin "30") (pinfunction "DGND_30") (pintype "passive"))
      (node (ref "U17") (pin "54") (pinfunction "DGND_54") (pintype "passive"))
    )
    (net (code "48") (name "Net-(C25-Pad1)") (class "Default")
      (node (ref "C25") (pin "1") (pinfunction "1_1") (pintype "passive"))
      (node (ref "C29") (pin "2") (pinfunction "2_2") (pintype "passive"))
      (node (ref "R19") (pin "1") (pinfunction "1_1") (pintype "passive"))
      (node (ref "U17") (pin "41") (pinfunction "AVdd_41") (pintype "passive"))
      (node (ref "U17") (pin "8") (pinfunction "AVdd_8") (pintype "passive"))
    )
    (net (code "49") (name "Net-(C26-Pad2)") (class "Default")
      (node (ref "C26") (pin "2") (pinfunction "2_2") (pintype "passive"))
      (node (ref "C30") (pin "1") (pinfunction "1_1") (pintype "passive"))
      (node (ref "R20") (pin "1") (pinfunction "1_1") (pintype "passive"))
      (node (ref "U17") (pin "11") (pinfunction "AVss_11") (pintype "passive"))
      (node (ref "U17") (pin "38") (pinfunction "AVss_38") (pintype "passive"))
    )
    (net (code "50") (name "Net-(D2-Pad2)") (class "Default")
      (node (ref "D2") (pin "2") (pinfunction "2_2") (pintype "passive"))
      (node (ref "R3") (pin "1") (pinfunction "1_1") (pintype "passive"))
    )
    (net (code "51") (name "Net-(J1-Pad2)") (class "Default")
      (node (ref "J1") (pin "2") (pinfunction "2_2") (pintype "passive"))
      (node (ref "R27") (pin "2") (pinfunction "2_2") (pintype "passive"))
    )
    (net (code "52") (name "Net-(J2-Pad2)") (class "Default")
      (node (ref "J2") (pin "2") (pinfunction "2_2") (pintype "passive"))
      (node (ref "R62") (pin "2") (pinfunction "2_2") (pintype "passive"))
    )
    (net (code "53") (name "Net-(R4-Pad2)") (class "Default")
      (node (ref "R4") (pin "2") (pinfunction "2_2") (pintype "passive"))
      (node (ref "U5") (pin "2") (pinfunction "2_2") (pintype "passive"))
    )
    (net (code "54") (name "Net-(R9-Pad2)") (class "Default")
      (node (ref "R9") (pin "2") (pinfunction "2_2") (pintype "passive"))
      (node (ref "U6") (pin "2") (pinfunction "2_2") (pintype "passive"))
    )
    (net (code "55") (name "Net-(S1-1b)") (class "Default")
      (node (ref "R54") (pin "2") (pinfunction "2_2") (pintype "passive"))
      (node (ref "S1") (pin "10") (pinfunction "1b_10") (pintype "passive"))
      (node (ref "U14") (pin "9") (pinfunction "Q3_9") (pintype "input"))
    )
    (net (code "56") (name "Net-(S1-2b)") (class "Default")
      (node (ref "R55") (pin "2") (pinfunction "2_2") (pintype "passive"))
      (node (ref "S1") (pin "9") (pinfunction "2b_9") (pintype "passive"))
      (node (ref "U14") (pin "12") (pinfunction "Q4_12") (pintype "input"))
    )
    (net (code "57") (name "Net-(S1-3b)") (class "Default")
      (node (ref "R56") (pin "2") (pinfunction "2_2") (pintype "passive"))
      (node (ref "S1") (pin "8") (pinfunction "3b_8") (pintype "passive"))
      (node (ref "U14") (pin "14") (pinfunction "Q5_14") (pintype "input"))
    )
    (net (code "58") (name "Net-(S1-4b)") (class "Default")
      (node (ref "R57") (pin "2") (pinfunction "2_2") (pintype "passive"))
      (node (ref "S1") (pin "7") (pinfunction "4b_7") (pintype "passive"))
      (node (ref "U14") (pin "16") (pinfunction "Q6_16") (pintype "input"))
    )
    (net (code "59") (name "Net-(S1-5b)") (class "Default")
      (node (ref "R58") (pin "2") (pinfunction "2_2") (pintype "passive"))
      (node (ref "S1") (pin "6") (pinfunction "5b_6") (pintype "passive"))
      (node (ref "U14") (pin "18") (pinfunction "Q7_18") (pintype "input"))
    )
    (net (code "60") (name "Net-(T1-G)") (class "Default")
      (node (ref "R2") (pin "2") (pinfunction "2_2") (pintype "passive"))
      (node (ref "T1") (pin "3") (pinfunction "G_3") (pintype "passive"))
      (node (ref "U5") (pin "4") (pinfunction "4_4") (pintype "passive"))
    )
    (net (code "61") (name "Net-(T2-G)") (class "Default")
      (node (ref "C3") (pin "2") (pinfunction "2_2") (pintype "passive"))
      (node (ref "R10") (pin "2") (pinfunction "2_2") (pintype "passive"))
      (node (ref "T2") (pin "3") (pinfunction "G_3") (pintype "passive"))
    )
    (net (code "62") (name "Net-(T3-D)") (class "Default")
      (node (ref "R4") (pin "1") (pinfunction "1_1") (pintype "passive"))
      (node (ref "R9") (pin "1") (pinfunction "1_1") (pintype "passive"))
      (node (ref "T3") (pin "3") (pinfunction "D_3") (pintype "passive"))
    )
    (net (code "63") (name "Net-(T3-G)") (class "Default")
      (node (ref "C14") (pin "1") (pinfunction "1_1") (pintype "passive"))
      (node (ref "R8") (pin "1") (pinfunction "1_1") (pintype "passive"))
      (node (ref "T3") (pin "1") (pinfunction "G_1") (pintype "passive"))
    )
    (net (code "64") (name "Net-(T4-D)") (class "Default")
      (node (ref "T4") (pin "3") (pinfunction "D_3") (pintype "passive"))
      (node (ref "U9") (pin "2") (pinfunction "In_2") (pintype "passive"))
    )
    (net (code "65") (name "Net-(T4-G)") (class "Default")
      (node (ref "R14") (pin "2") (pinfunction "2_2") (pintype "passive"))
      (node (ref "T4") (pin "1") (pinfunction "G_1") (pintype "passive"))
      (node (ref "U6") (pin "3") (pinfunction "3_3") (pintype "passive"))
    )
    (net (code "66") (name "Net-(T5-G)") (class "Default")
      (node (ref "C49") (pin "2") (pinfunction "2_2") (pintype "passive"))
      (node (ref "R44") (pin "2") (pinfunction "2_2") (pintype "passive"))
      (node (ref "T5") (pin "3") (pinfunction "G_3") (pintype "passive"))
    )
    (net (code "67") (name "Net-(U1-In)") (class "Default")
      (node (ref "T1") (pin "1") (pinfunction "D_1") (pintype "passive"))
      (node (ref "T1") (pin "2") (pinfunction "D_2") (pintype "passive"))
      (node (ref "T1") (pin "5") (pinfunction "D_5") (pintype "passive"))
      (node (ref "T1") (pin "6") (pinfunction "D_6") (pintype "passive"))
      (node (ref "U1") (pin "1") (pinfunction "In_1") (pintype "passive"))
    )
    (net (code "68") (name "Net-(U2-Vin)") (class "Default")
      (node (ref "C8") (pin "1") (pinfunction "1_1") (pintype "passive"))
      (node (ref "T2") (pin "1") (pinfunction "D_1") (pintype "passive"))
      (node (ref "T2") (pin "2") (pinfunction "D_2") (pintype "passive"))
      (node (ref "T2") (pin "5") (pinfunction "D_5") (pintype "passive"))
      (node (ref "T2") (pin "6") (pinfunction "D_6") (pintype "passive"))
      (node (ref "U2") (pin "2") (pinfunction "Vin_2") (pintype "passive"))
    )
    (net (code "69") (name "Net-(U2-Vout)") (class "Default")
      (node (ref "C11") (pin "1") (pinfunction "1_1") (pintype "passive"))
      (node (ref "R5") (pin "2") (pinfunction "2_2") (pintype "passive"))
      (node (ref "R50") (pin "1") (pinfunction "1_1") (pintype "passive"))
      (node (ref "TP6") (pin "1") (pinfunction "1_1") (pintype "passive"))
      (node (ref "U2") (pin "6") (pinfunction "Vout_sns_6") (pintype "passive"))
      (node (ref "U2") (pin "7") (pinfunction "Vout_7") (pintype "passive"))
    )
    (net (code "70") (name "Net-(U7-+)") (class "Default")
      (node (ref "R17") (pin "2") (pinfunction "2_2") (pintype "passive"))
      (node (ref "U7") (pin "3") (pinfunction "+_3") (pintype "passive"))
    )
    (net (code "71") (name "Net-(U7--)") (class "Default")
      (node (ref "R12") (pin "1") (pinfunction "1_1") (pintype "passive"))
      (node (ref "U7") (pin "2") (pinfunction "-_2") (pintype "passive"))
    )
    (net (code "72") (name "Net-(U7-OUT)") (class "Default")
      (node (ref "P1") (pin "1") (pinfunction "1_1") (pintype "passive"))
      (node (ref "R12") (pin "2") (pinfunction "2_2") (pintype "passive"))
      (node (ref "U7") (pin "6") (pinfunction "OUT_6") (pintype "passive"))
    )
    (net (code "73") (name "Net-(U7-V+)") (class "Default")
      (node (ref "C16") (pin "1") (pinfunction "1_1") (pintype "passive"))
      (node (ref "C18") (pin "1") (pinfunction "1_1") (pintype "passive"))
      (node (ref "R15") (pin "2") (pinfunction "2_2") (pintype "passive"))
      (node (ref "U7") (pin "7") (pinfunction "V+_7") (pintype "passive"))
    )
    (net (code "74") (name "Net-(U7-V-)") (class "Default")
      (node (ref "C20") (pin "1") (pinfunction "1_1") (pintype "passive"))
      (node (ref "C23") (pin "1") (pinfunction "1_1") (pintype "passive"))
      (node (ref "R22") (pin "2") (pinfunction "2_2") (pintype "passive"))
      (node (ref "U7") (pin "4") (pinfunction "V-_4") (pintype "passive"))
    )
    (net (code "75") (name "Net-(U8-+)") (class "Default")
      (node (ref "R18") (pin "2") (pinfunction "2_2") (pintype "passive"))
      (node (ref "U8") (pin "3") (pinfunction "+_3") (pintype "passive"))
    )
    (net (code "76") (name "Net-(U8--)") (class "Default")
      (node (ref "R13") (pin "1") (pinfunction "1_1") (pintype "passive"))
      (node (ref "U8") (pin "2") (pinfunction "-_2") (pintype "passive"))
    )
    (net (code "77") (name "Net-(U8-OUT)") (class "Default")
      (node (ref "P2") (pin "1") (pinfunction "1_1") (pintype "passive"))
      (node (ref "R13") (pin "2") (pinfunction "2_2") (pintype "passive"))
      (node (ref "U8") (pin "6") (pinfunction "OUT_6") (pintype "passive"))
    )
    (net (code "78") (name "Net-(U8-V+)") (class "Default")
      (node (ref "C17") (pin "1") (pinfunction "1_1") (pintype "passive"))
      (node (ref "C19") (pin "1") (pinfunction "1_1") (pintype "passive"))
      (node (ref "R16") (pin "2") (pinfunction "2_2") (pintype "passive"))
      (node (ref "U8") (pin "7") (pinfunction "V+_7") (pintype "passive"))
    )
    (net (code "79") (name "Net-(U8-V-)") (class "Default")
      (node (ref "C21") (pin "1") (pinfunction "1_1") (pintype "passive"))
      (node (ref "C24") (pin "1") (pinfunction "1_1") (pintype "passive"))
      (node (ref "R24") (pin "2") (pinfunction "2_2") (pintype "passive"))
      (node (ref "U8") (pin "4") (pinfunction "V-_4") (pintype "passive"))
    )
    (net (code "80") (name "Net-(U10-+)") (class "Default")
      (node (ref "R28") (pin "2") (pinfunction "2_2") (pintype "passive"))
      (node (ref "U10") (pin "3") (pinfunction "+_3") (pintype "passive"))
    )
    (net (code "81") (name "Net-(U10--)") (class "Default")
      (node (ref "R21") (pin "1") (pinfunction "1_1") (pintype "passive"))
      (node (ref "U10") (pin "2") (pinfunction "-_2") (pintype "passive"))
    )
    (net (code "82") (name "Net-(U10-OUT)") (class "Default")
      (node (ref "P3") (pin "1") (pinfunction "1_1") (pintype "passive"))
      (node (ref "R21") (pin "2") (pinfunction "2_2") (pintype "passive"))
      (node (ref "U10") (pin "6") (pinfunction "OUT_6") (pintype "passive"))
    )
    (net (code "83") (name "Net-(U10-V+)") (class "Default")
      (node (ref "C31") (pin "1") (pinfunction "1_1") (pintype "passive"))
      (node (ref "C33") (pin "1") (pinfunction "1_1") (pintype "passive"))
      (node (ref "R25") (pin "2") (pinfunction "2_2") (pintype "passive"))
      (node (ref "U10") (pin "7") (pinfunction "V+_7") (pintype "passive"))
    )
    (net (code "84") (name "Net-(U10-V-)") (class "Default")
      (node (ref "C37") (pin "1") (pinfunction "1_1") (pintype "passive"))
      (node (ref "C39") (pin "1") (pinfunction "1_1") (pintype "passive"))
      (node (ref "R31") (pin "2") (pinfunction "2_2") (pintype "passive"))
      (node (ref "U10") (pin "4") (pinfunction "V-_4") (pintype "passive"))
    )
    (net (code "85") (name "Net-(U11-+)") (class "Default")
      (node (ref "R29") (pin "2") (pinfunction "2_2") (pintype "passive"))
      (node (ref "U11") (pin "3") (pinfunction "+_3") (pintype "passive"))
    )
    (net (code "86") (name "Net-(U11--)") (class "Default")
      (node (ref "R23") (pin "1") (pinfunction "1_1") (pintype "passive"))
      (node (ref "U11") (pin "2") (pinfunction "-_2") (pintype "passive"))
    )
    (net (code "87") (name "Net-(U11-OUT)") (class "Default")
      (node (ref "P4") (pin "1") (pinfunction "1_1") (pintype "passive"))
      (node (ref "R23") (pin "2") (pinfunction "2_2") (pintype "passive"))
      (node (ref "U11") (pin "6") (pinfunction "OUT_6") (pintype "passive"))
    )
    (net (code "88") (name "Net-(U11-V+)") (class "Default")
      (node (ref "C32") (pin "1") (pinfunction "1_1") (pintype "passive"))
      (node (ref "C34") (pin "1") (pinfunction "1_1") (pintype "passive"))
      (node (ref "R26") (pin "2") (pinfunction "2_2") (pintype "passive"))
      (node (ref "U11") (pin "7") (pinfunction "V+_7") (pintype "passive"))
    )
    (net (code "89") (name "Net-(U11-V-)") (class "Default")
      (node (ref "C38") (pin "1") (pinfunction "1_1") (pintype "passive"))
      (node (ref "C40") (pin "1") (pinfunction "1_1") (pintype "passive"))
      (node (ref "R33") (pin "2") (pinfunction "2_2") (pintype "passive"))
      (node (ref "U11") (pin "4") (pinfunction "V-_4") (pintype "passive"))
    )
    (net (code "90") (name "Net-(U12-+)") (class "Default")
      (node (ref "R36") (pin "2") (pinfunction "2_2") (pintype "passive"))
      (node (ref "U12") (pin "3") (pinfunction "+_3") (pintype "passive"))
    )
    (net (code "91") (name "Net-(U12--)") (class "Default")
      (node (ref "R30") (pin "1") (pinfunction "1_1") (pintype "passive"))
      (node (ref "U12") (pin "2") (pinfunction "-_2") (pintype "passive"))
    )
    (net (code "92") (name "Net-(U12-OUT)") (class "Default")
      (node (ref "P5") (pin "1") (pinfunction "1_1") (pintype "passive"))
      (node (ref "R30") (pin "2") (pinfunction "2_2") (pintype "passive"))
      (node (ref "U12") (pin "6") (pinfunction "OUT_6") (pintype "passive"))
    )
    (net (code "93") (name "Net-(U12-V+)") (class "Default")
      (node (ref "C41") (pin "1") (pinfunction "1_1") (pintype "passive"))
      (node (ref "C43") (pin "1") (pinfunction "1_1") (pintype "passive"))
      (node (ref "R34") (pin "2") (pinfunction "2_2") (pintype "passive"))
      (node (ref "U12") (pin "7") (pinfunction "V+_7") (pintype "passive"))
    )
    (net (code "94") (name "Net-(U12-V-)") (class "Default")
      (node (ref "C45") (pin "1") (pinfunction "1_1") (pintype "passive"))
      (node (ref "C47") (pin "1") (pinfunction "1_1") (pintype "passive"))
      (node (ref "R39") (pin "2") (pinfunction "2_2") (pintype "passive"))
      (node (ref "U12") (pin "4") (pinfunction "V-_4") (pintype "passive"))
    )
    (net (code "95") (name "Net-(U13-+)") (class "Default")
      (node (ref "R37") (pin "2") (pinfunction "2_2") (pintype "passive"))
      (node (ref "U13") (pin "3") (pinfunction "+_3") (pintype "passive"))
    )
    (net (code "96") (name "Net-(U13--)") (class "Default")
      (node (ref "R32") (pin "1") (pinfunction "1_1") (pintype "passive"))
      (node (ref "U13") (pin "2") (pinfunction "-_2") (pintype "passive"))
    )
    (net (code "97") (name "Net-(U13-OUT)") (class "Default")
      (node (ref "P6") (pin "1") (pinfunction "1_1") (pintype "passive"))
      (node (ref "R32") (pin "2") (pinfunction "2_2") (pintype "passive"))
      (node (ref "U13") (pin "6") (pinfunction "OUT_6") (pintype "passive"))
    )
    (net (code "98") (name "Net-(U13-V+)") (class "Default")
      (node (ref "C42") (pin "1") (pinfunction "1_1") (pintype "passive"))
      (node (ref "C44") (pin "1") (pinfunction "1_1") (pintype "passive"))
      (node (ref "R35") (pin "2") (pinfunction "2_2") (pintype "passive"))
      (node (ref "U13") (pin "7") (pinfunction "V+_7") (pintype "passive"))
    )
    (net (code "99") (name "Net-(U13-V-)") (class "Default")
      (node (ref "C46") (pin "1") (pinfunction "1_1") (pintype "passive"))
      (node (ref "C48") (pin "1") (pinfunction "1_1") (pintype "passive"))
      (node (ref "R41") (pin "2") (pinfunction "2_2") (pintype "passive"))
      (node (ref "U13") (pin "4") (pinfunction "V-_4") (pintype "passive"))
    )
    (net (code "100") (name "Net-(U14-~{P=Q})") (class "Default")
      (node (ref "U14") (pin "19") (pinfunction "~{P=Q}_19") (pintype "output"))
      (node (ref "U17") (pin "58") (pinfunction "~{CS}_58") (pintype "input"))
    )
    (net (code "101") (name "Net-(U15-+)") (class "Default")
      (node (ref "R46") (pin "2") (pinfunction "2_2") (pintype "passive"))
      (node (ref "U15") (pin "3") (pinfunction "+_3") (pintype "passive"))
    )
    (net (code "102") (name "Net-(U15--)") (class "Default")
      (node (ref "R38") (pin "1") (pinfunction "1_1") (pintype "passive"))
      (node (ref "U15") (pin "2") (pinfunction "-_2") (pintype "passive"))
    )
    (net (code "103") (name "Net-(U15-OUT)") (class "Default")
      (node (ref "P7") (pin "1") (pinfunction "1_1") (pintype "passive"))
      (node (ref "R38") (pin "2") (pinfunction "2_2") (pintype "passive"))
      (node (ref "U15") (pin "6") (pinfunction "OUT_6") (pintype "passive"))
    )
    (net (code "104") (name "Net-(U15-V+)") (class "Default")
      (node (ref "C50") (pin "1") (pinfunction "1_1") (pintype "passive"))
      (node (ref "C52") (pin "1") (pinfunction "1_1") (pintype "passive"))
      (node (ref "R42") (pin "2") (pinfunction "2_2") (pintype "passive"))
      (node (ref "U15") (pin "7") (pinfunction "V+_7") (pintype "passive"))
    )
    (net (code "105") (name "Net-(U15-V-)") (class "Default")
      (node (ref "C54") (pin "1") (pinfunction "1_1") (pintype "passive"))
      (node (ref "C56") (pin "1") (pinfunction "1_1") (pintype "passive"))
      (node (ref "R48") (pin "2") (pinfunction "2_2") (pintype "passive"))
      (node (ref "U15") (pin "4") (pinfunction "V-_4") (pintype "passive"))
    )
    (net (code "106") (name "Net-(U16-+)") (class "Default")
      (node (ref "R47") (pin "2") (pinfunction "2_2") (pintype "passive"))
      (node (ref "U16") (pin "3") (pinfunction "+_3") (pintype "passive"))
    )
    (net (code "107") (name "Net-(U16--)") (class "Default")
      (node (ref "R40") (pin "1") (pinfunction "1_1") (pintype "passive"))
      (node (ref "U16") (pin "2") (pinfunction "-_2") (pintype "passive"))
    )
    (net (code "108") (name "Net-(U16-OUT)") (class "Default")
      (node (ref "P8") (pin "1") (pinfunction "1_1") (pintype "passive"))
      (node (ref "R40") (pin "2") (pinfunction "2_2") (pintype "passive"))
      (node (ref "U16") (pin "6") (pinfunction "OUT_6") (pintype "passive"))
    )
    (net (code "109") (name "Net-(U16-V+)") (class "Default")
      (node (ref "C51") (pin "1") (pinfunction "1_1") (pintype "passive"))
      (node (ref "C53") (pin "1") (pinfunction "1_1") (pintype "passive"))
      (node (ref "R43") (pin "2") (pinfunction "2_2") (pintype "passive"))
      (node (ref "U16") (pin "7") (pinfunction "V+_7") (pintype "passive"))
    )
    (net (code "110") (name "Net-(U16-V-)") (class "Default")
      (node (ref "C55") (pin "1") (pinfunction "1_1") (pintype "passive"))
      (node (ref "C57") (pin "1") (pinfunction "1_1") (pintype "passive"))
      (node (ref "R49") (pin "2") (pinfunction "2_2") (pintype "passive"))
      (node (ref "U16") (pin "4") (pinfunction "V-_4") (pintype "passive"))
    )
    (net (code "111") (name "Net-(U17-A3)") (class "Default")
      (node (ref "R51") (pin "2") (pinfunction "2_2") (pintype "passive"))
      (node (ref "U17") (pin "27") (pinfunction "A3_27") (pintype "input"))
    )
    (net (code "112") (name "Net-(U17-A4)") (class "Default")
      (node (ref "R52") (pin "2") (pinfunction "2_2") (pintype "passive"))
      (node (ref "U17") (pin "29") (pinfunction "A4_29") (pintype "input"))
    )
    (net (code "113") (name "Net-(U17-BUSY)") (class "Default")
      (node (ref "R64") (pin "1") (pinfunction "1_1") (pintype "passive"))
      (node (ref "TP5") (pin "1") (pinfunction "1_1") (pintype "passive"))
      (node (ref "U17") (pin "16") (pinfunction "BUSY_16") (pintype "output"))
    )
    (net (code "114") (name "Net-(U17-GPIO)") (class "Default")
      (node (ref "R63") (pin "1") (pinfunction "1_1") (pintype "passive"))
      (node (ref "TP4") (pin "1") (pinfunction "1_1") (pintype "passive"))
      (node (ref "U17") (pin "33") (pinfunction "GPIO_33") (pintype "bidirectional"))
    )
    (net (code "115") (name "Net-(U17-OFFSET-A)") (class "Default")
      (node (ref "TP2") (pin "1") (pinfunction "1_1") (pintype "passive"))
      (node (ref "U17") (pin "12") (pinfunction "OFFSET-A_12") (pintype "passive"))
    )
    (net (code "116") (name "Net-(U17-OFFSET-B)") (class "Default")
      (node (ref "TP3") (pin "1") (pinfunction "1_1") (pintype "passive"))
      (node (ref "U17") (pin "37") (pinfunction "OFFSET-B_37") (pintype "passive"))
    )
    (net (code "117") (name "Net-(U17-REF-A)") (class "Default")
      (node (ref "C9") (pin "1") (pinfunction "1_1") (pintype "passive"))
      (node (ref "R62") (pin "1") (pinfunction "1_1") (pintype "passive"))
      (node (ref "TP8") (pin "1") (pinfunction "1_1") (pintype "passive"))
      (node (ref "U17") (pin "6") (pinfunction "REF-A_6") (pintype "passive"))
    )
    (net (code "118") (name "Net-(U17-REF-B)") (class "Default")
      (node (ref "C35") (pin "1") (pinfunction "1_1") (pintype "passive"))
      (node (ref "R27") (pin "1") (pinfunction "1_1") (pintype "passive"))
      (node (ref "TP7") (pin "1") (pinfunction "1_1") (pintype "passive"))
      (node (ref "U17") (pin "43") (pinfunction "REF-B_43") (pintype "passive"))
    )
    (net (code "119") (name "Net-(U17-RSTSEL)") (class "Default")
      (node (ref "R59") (pin "2") (pinfunction "2_2") (pintype "passive"))
      (node (ref "U17") (pin "34") (pinfunction "RSTSEL_34") (pintype "input"))
    )
    (net (code "120") (name "Net-(U17-R{slash}~{W})") (class "Default")
      (node (ref "R53") (pin "2") (pinfunction "2_2") (pintype "passive"))
      (node (ref "U17") (pin "57") (pinfunction "R/~{W}_57") (pintype "input"))
    )
    (net (code "121") (name "Net-(U17-Vmon)") (class "Default")
      (node (ref "TP1") (pin "1") (pinfunction "1_1") (pintype "passive"))
      (node (ref "U17") (pin "4") (pinfunction "Vmon_4") (pintype "passive"))
    )
    (net (code "122") (name "Net-(U17-~{CLR})") (class "Default")
      (node (ref "R45") (pin "2") (pinfunction "2_2") (pintype "passive"))
      (node (ref "T5") (pin "1") (pinfunction "D_1") (pintype "passive"))
      (node (ref "T5") (pin "2") (pinfunction "D_2") (pintype "passive"))
      (node (ref "T5") (pin "5") (pinfunction "D_5") (pintype "passive"))
      (node (ref "T5") (pin "6") (pinfunction "D_6") (pintype "passive"))
      (node (ref "U17") (pin "17") (pinfunction "~{CLR}_17") (pintype "input"))
      (node (ref "U17") (pin "19") (pinfunction "~{RST}_19") (pintype "input"))
    )
    (net (code "123") (name "Net-(U17-~{LDAC})") (class "Default")
      (node (ref "R60") (pin "2") (pinfunction "2_2") (pintype "passive"))
      (node (ref "U17") (pin "18") (pinfunction "~{LDAC}_18") (pintype "input"))
    )
    (net (code "124") (name "Net-(U17-~{USB}{slash}BTC)") (class "Default")
      (node (ref "R61") (pin "2") (pinfunction "2_2") (pintype "passive"))
      (node (ref "U17") (pin "15") (pinfunction "~{USB}/BTC_15") (pintype "input"))
    )
    (net (code "125") (name "unconnected-(U2-nc-Pad1)") (class "Default")
      (node (ref "U2") (pin "1") (pinfunction "nc_1") (pintype "passive"))
    )
    (net (code "126") (name "unconnected-(U2-nc-Pad5)") (class "Default")
      (node (ref "U2") (pin "5") (pinfunction "nc_5") (pintype "passive"))
    )
    (net (code "127") (name "unconnected-(U2-nc-Pad8)") (class "Default")
      (node (ref "U2") (pin "8") (pinfunction "nc_8") (pintype "passive"))
    )
    (net (code "128") (name "unconnected-(U17-nc-Pad14)") (class "Default")
      (node (ref "U17") (pin "14") (pinfunction "nc_14") (pintype "passive"))
    )
    (net (code "129") (name "unconnected-(U17-nc-Pad22)") (class "Default")
      (node (ref "U17") (pin "22") (pinfunction "nc_22") (pintype "passive"))
    )
    (net (code "130") (name "unconnected-(U17-nc-Pad23)") (class "Default")
      (node (ref "U17") (pin "23") (pinfunction "nc_23") (pintype "passive"))
    )
    (net (code "131") (name "unconnected-(U17-nc-Pad28)") (class "Default")
      (node (ref "U17") (pin "28") (pinfunction "nc_28") (pintype "passive"))
    )
    (net (code "132") (name "unconnected-(U17-nc-Pad31)") (class "Default")
      (node (ref "U17") (pin "31") (pinfunction "nc_31") (pintype "passive"))
    )
    (net (code "133") (name "unconnected-(U17-nc-Pad32)") (class "Default")
      (node (ref "U17") (pin "32") (pinfunction "nc_32") (pintype "passive"))
    )
    (net (code "134") (name "unconnected-(U17-nc-Pad35)") (class "Default")
      (node (ref "U17") (pin "35") (pinfunction "nc_35") (pintype "passive"))
    )
    (net (code "135") (name "unconnected-(U17-nc-Pad45)") (class "Default")
      (node (ref "U17") (pin "45") (pinfunction "nc_45") (pintype "passive"))
    )
    (net (code "136") (name "unconnected-(U17-nc-Pad53)") (class "Default")
      (node (ref "U17") (pin "53") (pinfunction "nc_53") (pintype "passive"))
    )
  )
)
